# PCB_Ver_1_0.net
KiCad netlist of a schematic drawn in Altium Designer
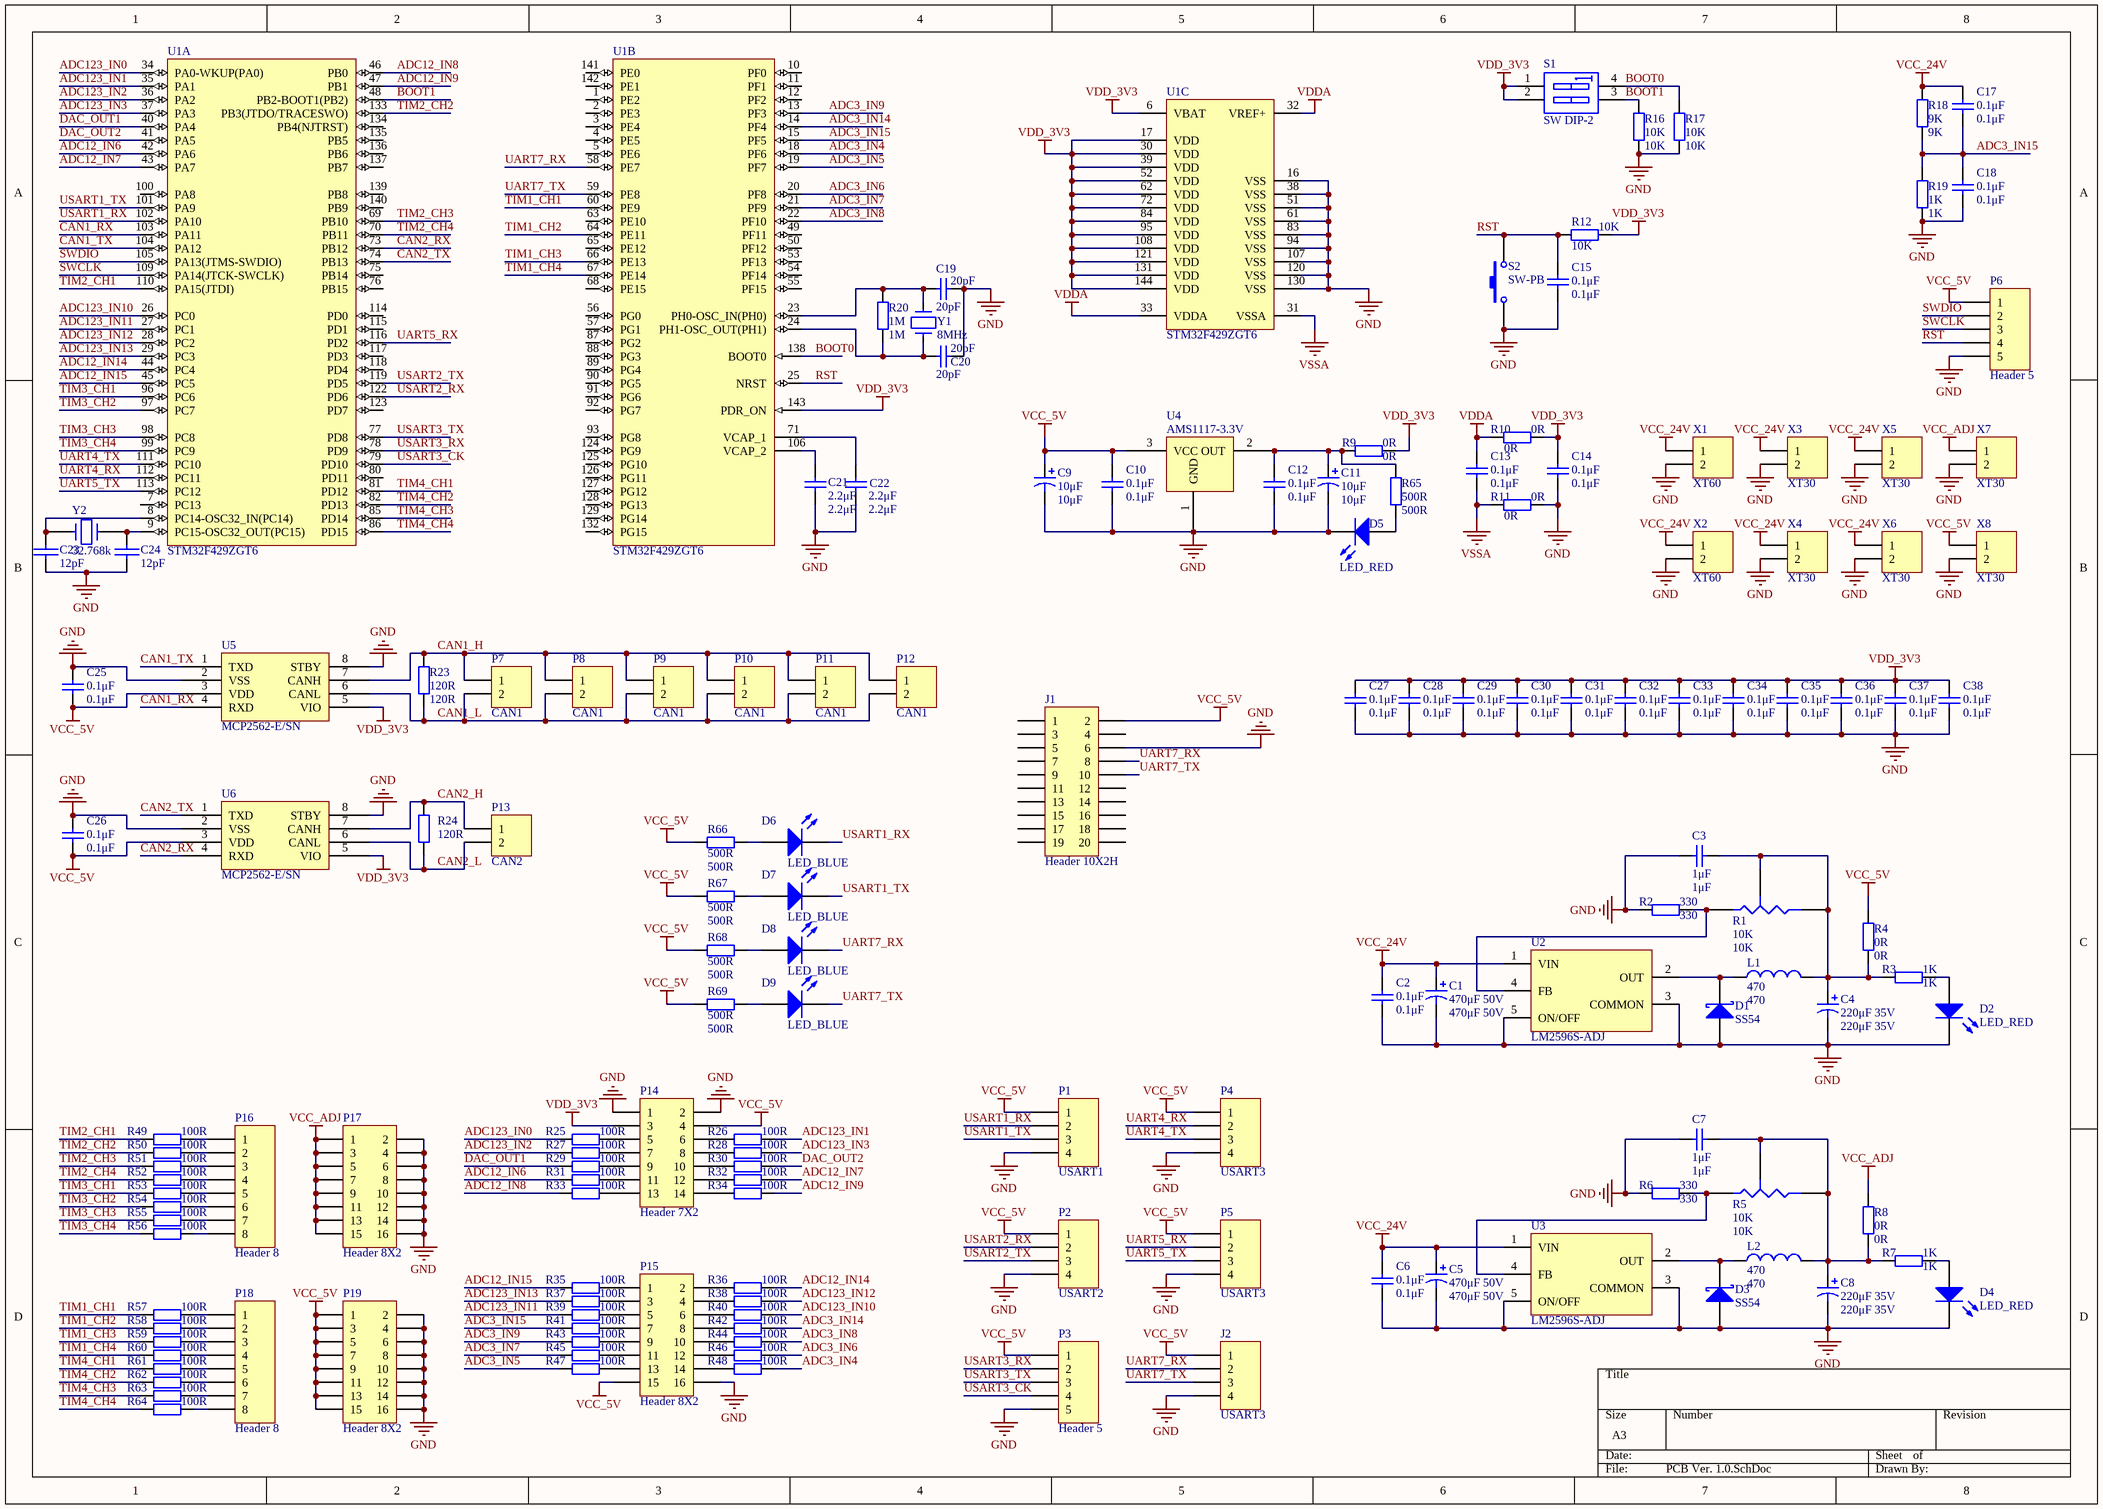
[diagram p0: PCB Ver. 1.0.SchDoc]

(export (version "E")
  (design (tool "Eeschema 10.0.6"))
  (components
    (comp (ref "C1")
      (value "470μF 50V")
      (footprint "RB-.2/.4")
      (description "Polarized Capacitor (Radial)")
      (fields (field (name "ALTIUM_VALUE") "470μF 50V") (field (name "PUBLISHER") "Altium Limited"))
      (libsource (lib "Miscellaneous Devices") (part "Cap Pol1"))
    )
    (comp (ref "C2")
      (value "0.1μF")
      (footprint "0805")
      (description "Capacitor")
      (fields (field (name "ALTIUM_VALUE") "0.1μF") (field (name "PUBLISHER") "Altium Limited"))
      (libsource (lib "Miscellaneous Devices") (part "Cap"))
    )
    (comp (ref "C3")
      (value "1μF")
      (footprint "0805")
      (description "Capacitor")
      (fields (field (name "ALTIUM_VALUE") "1μF") (field (name "PUBLISHER") "Altium Limited"))
      (libsource (lib "Miscellaneous Devices") (part "Cap"))
    )
    (comp (ref "C4")
      (value "220μF 35V")
      (footprint "RB-.2/.4")
      (description "Polarized Capacitor (Radial)")
      (fields (field (name "ALTIUM_VALUE") "220μF 35V") (field (name "PUBLISHER") "Altium Limited"))
      (libsource (lib "Miscellaneous Devices") (part "Cap Pol1"))
    )
    (comp (ref "C5")
      (value "470μF 50V")
      (footprint "RB-.2/.4")
      (description "Polarized Capacitor (Radial)")
      (fields (field (name "ALTIUM_VALUE") "470μF 50V") (field (name "PUBLISHER") "Altium Limited"))
      (libsource (lib "Miscellaneous Devices") (part "Cap Pol1"))
    )
    (comp (ref "C6")
      (value "0.1μF")
      (footprint "0805")
      (description "Capacitor")
      (fields (field (name "ALTIUM_VALUE") "0.1μF") (field (name "PUBLISHER") "Altium Limited"))
      (libsource (lib "Miscellaneous Devices") (part "Cap"))
    )
    (comp (ref "C7")
      (value "1μF")
      (footprint "0805")
      (description "Capacitor")
      (fields (field (name "ALTIUM_VALUE") "1μF") (field (name "PUBLISHER") "Altium Limited"))
      (libsource (lib "Miscellaneous Devices") (part "Cap"))
    )
    (comp (ref "C8")
      (value "220μF 35V")
      (footprint "RB-.2/.4")
      (description "Polarized Capacitor (Radial)")
      (fields (field (name "ALTIUM_VALUE") "220μF 35V") (field (name "PUBLISHER") "Altium Limited"))
      (libsource (lib "Miscellaneous Devices") (part "Cap Pol1"))
    )
    (comp (ref "C9")
      (value "10μF")
      (footprint "0805")
      (description "Polarized Capacitor (Radial)")
      (fields (field (name "ALTIUM_VALUE") "10μF") (field (name "PUBLISHER") "Altium Limited"))
      (libsource (lib "Miscellaneous Devices") (part "Cap Pol1"))
    )
    (comp (ref "C10")
      (value "0.1μF")
      (footprint "0805")
      (description "Capacitor")
      (fields (field (name "ALTIUM_VALUE") "0.1μF") (field (name "PUBLISHER") "Altium Limited"))
      (libsource (lib "Miscellaneous Devices") (part "Cap"))
    )
    (comp (ref "C11")
      (value "10μF")
      (footprint "0805")
      (description "Polarized Capacitor (Radial)")
      (fields (field (name "ALTIUM_VALUE") "10μF") (field (name "PUBLISHER") "Altium Limited"))
      (libsource (lib "Miscellaneous Devices") (part "Cap Pol1"))
    )
    (comp (ref "C12")
      (value "0.1μF")
      (footprint "0805")
      (description "Capacitor")
      (fields (field (name "ALTIUM_VALUE") "0.1μF") (field (name "PUBLISHER") "Altium Limited"))
      (libsource (lib "Miscellaneous Devices") (part "Cap"))
    )
    (comp (ref "C13")
      (value "0.1μF")
      (footprint "0805")
      (description "Capacitor")
      (fields (field (name "ALTIUM_VALUE") "0.1μF") (field (name "PUBLISHER") "Altium Limited"))
      (libsource (lib "Miscellaneous Devices") (part "Cap"))
    )
    (comp (ref "C14")
      (value "0.1μF")
      (footprint "0805")
      (description "Capacitor")
      (fields (field (name "ALTIUM_VALUE") "0.1μF") (field (name "PUBLISHER") "Altium Limited"))
      (libsource (lib "Miscellaneous Devices") (part "Cap"))
    )
    (comp (ref "C15")
      (value "0.1μF")
      (footprint "0805")
      (description "Capacitor")
      (fields (field (name "ALTIUM_VALUE") "0.1μF") (field (name "PUBLISHER") "Altium Limited"))
      (libsource (lib "Miscellaneous Devices") (part "Cap"))
    )
    (comp (ref "C17")
      (value "0.1μF")
      (footprint "0805")
      (description "Capacitor")
      (fields (field (name "ALTIUM_VALUE") "0.1μF") (field (name "PUBLISHER") "Altium Limited"))
      (libsource (lib "Miscellaneous Devices") (part "Cap"))
    )
    (comp (ref "C18")
      (value "0.1μF")
      (footprint "0805")
      (description "Capacitor")
      (fields (field (name "ALTIUM_VALUE") "0.1μF") (field (name "PUBLISHER") "Altium Limited"))
      (libsource (lib "Miscellaneous Devices") (part "Cap"))
    )
    (comp (ref "C19")
      (value "20pF")
      (footprint "0805")
      (description "Capacitor")
      (fields (field (name "ALTIUM_VALUE") "20pF") (field (name "PUBLISHER") "Altium Limited"))
      (libsource (lib "Miscellaneous Devices") (part "Cap"))
    )
    (comp (ref "C20")
      (value "20pF")
      (footprint "0805")
      (description "Capacitor")
      (fields (field (name "ALTIUM_VALUE") "20pF") (field (name "PUBLISHER") "Altium Limited"))
      (libsource (lib "Miscellaneous Devices") (part "Cap"))
    )
    (comp (ref "C21")
      (value "2.2μF")
      (footprint "0805")
      (description "Capacitor")
      (fields (field (name "ALTIUM_VALUE") "2.2μF") (field (name "PUBLISHER") "Altium Limited"))
      (libsource (lib "Miscellaneous Devices") (part "Cap"))
    )
    (comp (ref "C22")
      (value "2.2μF")
      (footprint "0805")
      (description "Capacitor")
      (fields (field (name "ALTIUM_VALUE") "2.2μF") (field (name "PUBLISHER") "Altium Limited"))
      (libsource (lib "Miscellaneous Devices") (part "Cap"))
    )
    (comp (ref "C23")
      (value "12pF")
      (footprint "0805")
      (description "Capcitor")
      (libsource (lib "LXKJSJ") (part "CAP"))
    )
    (comp (ref "C24")
      (value "12pF")
      (footprint "0805")
      (description "Capcitor")
      (libsource (lib "LXKJSJ") (part "CAP"))
    )
    (comp (ref "C25")
      (value "0.1μF")
      (footprint "0805")
      (description "Capacitor")
      (fields (field (name "ALTIUM_VALUE") "0.1μF") (field (name "PUBLISHER") "Altium Limited"))
      (libsource (lib "Miscellaneous Devices") (part "Cap"))
    )
    (comp (ref "C26")
      (value "0.1μF")
      (footprint "0805")
      (description "Capacitor")
      (fields (field (name "ALTIUM_VALUE") "0.1μF") (field (name "PUBLISHER") "Altium Limited"))
      (libsource (lib "Miscellaneous Devices") (part "Cap"))
    )
    (comp (ref "C27")
      (value "0.1μF")
      (footprint "0805")
      (description "Capacitor")
      (fields (field (name "ALTIUM_VALUE") "0.1μF") (field (name "PUBLISHER") "Altium Limited"))
      (libsource (lib "Miscellaneous Devices") (part "Cap"))
    )
    (comp (ref "C28")
      (value "0.1μF")
      (footprint "0805")
      (description "Capacitor")
      (fields (field (name "ALTIUM_VALUE") "0.1μF") (field (name "PUBLISHER") "Altium Limited"))
      (libsource (lib "Miscellaneous Devices") (part "Cap"))
    )
    (comp (ref "C29")
      (value "0.1μF")
      (footprint "0805")
      (description "Capacitor")
      (fields (field (name "ALTIUM_VALUE") "0.1μF") (field (name "PUBLISHER") "Altium Limited"))
      (libsource (lib "Miscellaneous Devices") (part "Cap"))
    )
    (comp (ref "C30")
      (value "0.1μF")
      (footprint "0805")
      (description "Capacitor")
      (fields (field (name "ALTIUM_VALUE") "0.1μF") (field (name "PUBLISHER") "Altium Limited"))
      (libsource (lib "Miscellaneous Devices") (part "Cap"))
    )
    (comp (ref "C31")
      (value "0.1μF")
      (footprint "0805")
      (description "Capacitor")
      (fields (field (name "ALTIUM_VALUE") "0.1μF") (field (name "PUBLISHER") "Altium Limited"))
      (libsource (lib "Miscellaneous Devices") (part "Cap"))
    )
    (comp (ref "C32")
      (value "0.1μF")
      (footprint "0805")
      (description "Capacitor")
      (fields (field (name "ALTIUM_VALUE") "0.1μF") (field (name "PUBLISHER") "Altium Limited"))
      (libsource (lib "Miscellaneous Devices") (part "Cap"))
    )
    (comp (ref "C33")
      (value "0.1μF")
      (footprint "0805")
      (description "Capacitor")
      (fields (field (name "ALTIUM_VALUE") "0.1μF") (field (name "PUBLISHER") "Altium Limited"))
      (libsource (lib "Miscellaneous Devices") (part "Cap"))
    )
    (comp (ref "C34")
      (value "0.1μF")
      (footprint "0805")
      (description "Capacitor")
      (fields (field (name "ALTIUM_VALUE") "0.1μF") (field (name "PUBLISHER") "Altium Limited"))
      (libsource (lib "Miscellaneous Devices") (part "Cap"))
    )
    (comp (ref "C35")
      (value "0.1μF")
      (footprint "0805")
      (description "Capacitor")
      (fields (field (name "ALTIUM_VALUE") "0.1μF") (field (name "PUBLISHER") "Altium Limited"))
      (libsource (lib "Miscellaneous Devices") (part "Cap"))
    )
    (comp (ref "C36")
      (value "0.1μF")
      (footprint "0805")
      (description "Capacitor")
      (fields (field (name "ALTIUM_VALUE") "0.1μF") (field (name "PUBLISHER") "Altium Limited"))
      (libsource (lib "Miscellaneous Devices") (part "Cap"))
    )
    (comp (ref "C37")
      (value "0.1μF")
      (footprint "0805")
      (description "Capacitor")
      (fields (field (name "ALTIUM_VALUE") "0.1μF") (field (name "PUBLISHER") "Altium Limited"))
      (libsource (lib "Miscellaneous Devices") (part "Cap"))
    )
    (comp (ref "C38")
      (value "0.1μF")
      (footprint "0805")
      (description "Capacitor")
      (fields (field (name "ALTIUM_VALUE") "0.1μF") (field (name "PUBLISHER") "Altium Limited"))
      (libsource (lib "Miscellaneous Devices") (part "Cap"))
    )
    (comp (ref "D1")
      (value "SS54")
      (footprint "DO-214AA")
      (description "Schottky Rectifier")
      (fields (field (name "PUBLISHER") "Altium Limited"))
      (libsource (lib "Miscellaneous Devices") (part "Diode 11DQ03"))
    )
    (comp (ref "D2")
      (value "LED_RED")
      (footprint "1206_LED")
      (description "Typical BLUE SiC LED")
      (fields (field (name "PUBLISHER") "Altium Limited"))
      (libsource (lib "Miscellaneous Devices") (part "LED3"))
    )
    (comp (ref "D3")
      (value "SS54")
      (footprint "DO-214AA")
      (description "Schottky Rectifier")
      (fields (field (name "PUBLISHER") "Altium Limited"))
      (libsource (lib "Miscellaneous Devices") (part "Diode 11DQ03"))
    )
    (comp (ref "D4")
      (value "LED_RED")
      (footprint "1206_LED")
      (description "Typical BLUE SiC LED")
      (fields (field (name "PUBLISHER") "Altium Limited"))
      (libsource (lib "Miscellaneous Devices") (part "LED3"))
    )
    (comp (ref "D5")
      (value "LED_RED")
      (footprint "1206_LED")
      (description "Typical BLUE SiC LED")
      (fields (field (name "PUBLISHER") "Altium Limited"))
      (libsource (lib "Miscellaneous Devices") (part "LED3"))
    )
    (comp (ref "D6")
      (value "LED_BLUE")
      (footprint "1206_LED")
      (description "Typical BLUE SiC LED")
      (fields (field (name "PUBLISHER") "Altium Limited"))
      (libsource (lib "Miscellaneous Devices") (part "LED3"))
    )
    (comp (ref "D7")
      (value "LED_BLUE")
      (footprint "1206_LED")
      (description "Typical BLUE SiC LED")
      (fields (field (name "PUBLISHER") "Altium Limited"))
      (libsource (lib "Miscellaneous Devices") (part "LED3"))
    )
    (comp (ref "D8")
      (value "LED_BLUE")
      (footprint "1206_LED")
      (description "Typical BLUE SiC LED")
      (fields (field (name "PUBLISHER") "Altium Limited"))
      (libsource (lib "Miscellaneous Devices") (part "LED3"))
    )
    (comp (ref "D9")
      (value "LED_BLUE")
      (footprint "1206_LED")
      (description "Typical BLUE SiC LED")
      (fields (field (name "PUBLISHER") "Altium Limited"))
      (libsource (lib "Miscellaneous Devices") (part "LED3"))
    )
    (comp (ref "J1")
      (value "Header 10X2H")
      (footprint "HDR2X10")
      (description "Header, 10-Pin, Dual row, Right Angle")
      (fields (field (name "PUBLISHER") "Altium Limited"))
      (libsource (lib "Miscellaneous Connectors") (part "Header 10X2H"))
    )
    (comp (ref "J2")
      (value "USART3")
      (footprint "HDR1X4")
      (description "Header, 4-Pin")
      (fields (field (name "PUBLISHER") "Altium Limited"))
      (libsource (lib "Miscellaneous Connectors") (part "Header 4"))
    )
    (comp (ref "L1")
      (value "470")
      (footprint "12*12*7贴片电感")
      (description "Inductor")
      (fields (field (name "ALTIUM_VALUE") "470") (field (name "PUBLISHER") "Altium Limited"))
      (libsource (lib "Miscellaneous Devices") (part "Inductor"))
    )
    (comp (ref "L2")
      (value "470")
      (footprint "12*12*7贴片电感")
      (description "Inductor")
      (fields (field (name "ALTIUM_VALUE") "470") (field (name "PUBLISHER") "Altium Limited"))
      (libsource (lib "Miscellaneous Devices") (part "Inductor"))
    )
    (comp (ref "P1")
      (value "USART1")
      (footprint "HDR1X4")
      (description "Header, 4-Pin")
      (fields (field (name "PUBLISHER") "Altium Limited"))
      (libsource (lib "Miscellaneous Connectors") (part "Header 4"))
    )
    (comp (ref "P2")
      (value "USART2")
      (footprint "HDR1X4")
      (description "Header, 4-Pin")
      (fields (field (name "PUBLISHER") "Altium Limited"))
      (libsource (lib "Miscellaneous Connectors") (part "Header 4"))
    )
    (comp (ref "P3")
      (value "Header 5")
      (footprint "HDR1X5")
      (description "Header, 5-Pin")
      (fields (field (name "PUBLISHER") "Altium Limited"))
      (libsource (lib "Miscellaneous Connectors") (part "Header 5"))
    )
    (comp (ref "P4")
      (value "USART3")
      (footprint "HDR1X4")
      (description "Header, 4-Pin")
      (fields (field (name "PUBLISHER") "Altium Limited"))
      (libsource (lib "Miscellaneous Connectors") (part "Header 4"))
    )
    (comp (ref "P5")
      (value "USART3")
      (footprint "HDR1X4")
      (description "Header, 4-Pin")
      (fields (field (name "PUBLISHER") "Altium Limited"))
      (libsource (lib "Miscellaneous Connectors") (part "Header 4"))
    )
    (comp (ref "P6")
      (value "Header 5")
      (footprint "HDR1X5")
      (description "Header, 5-Pin")
      (fields (field (name "PUBLISHER") "Altium Limited"))
      (libsource (lib "Miscellaneous Connectors") (part "Header 5"))
    )
    (comp (ref "P7")
      (value "CAN1")
      (footprint "HDR1X2")
      (description "Header, 2-Pin")
      (fields (field (name "PUBLISHER") "Altium Limited"))
      (libsource (lib "Miscellaneous Connectors") (part "Header 2"))
    )
    (comp (ref "P8")
      (value "CAN1")
      (footprint "HDR1X2")
      (description "Header, 2-Pin")
      (fields (field (name "PUBLISHER") "Altium Limited"))
      (libsource (lib "Miscellaneous Connectors") (part "Header 2"))
    )
    (comp (ref "P9")
      (value "CAN1")
      (footprint "HDR1X2")
      (description "Header, 2-Pin")
      (fields (field (name "PUBLISHER") "Altium Limited"))
      (libsource (lib "Miscellaneous Connectors") (part "Header 2"))
    )
    (comp (ref "P10")
      (value "CAN1")
      (footprint "HDR1X2")
      (description "Header, 2-Pin")
      (fields (field (name "PUBLISHER") "Altium Limited"))
      (libsource (lib "Miscellaneous Connectors") (part "Header 2"))
    )
    (comp (ref "P11")
      (value "CAN1")
      (footprint "HDR1X2")
      (description "Header, 2-Pin")
      (fields (field (name "PUBLISHER") "Altium Limited"))
      (libsource (lib "Miscellaneous Connectors") (part "Header 2"))
    )
    (comp (ref "P12")
      (value "CAN1")
      (footprint "HDR1X2")
      (description "Header, 2-Pin")
      (fields (field (name "PUBLISHER") "Altium Limited"))
      (libsource (lib "Miscellaneous Connectors") (part "Header 2"))
    )
    (comp (ref "P13")
      (value "CAN2")
      (footprint "HDR1X2")
      (description "Header, 2-Pin")
      (fields (field (name "PUBLISHER") "Altium Limited"))
      (libsource (lib "Miscellaneous Connectors") (part "Header 2"))
    )
    (comp (ref "P14")
      (value "Header 7X2")
      (footprint "HDR2X7")
      (description "Header, 7-Pin, Dual row")
      (fields (field (name "PUBLISHER") "Altium Limited"))
      (libsource (lib "Miscellaneous Connectors") (part "Header 7X2"))
    )
    (comp (ref "P15")
      (value "Header 8X2")
      (footprint "HDR2X8")
      (description "Header, 8-Pin, Dual row")
      (fields (field (name "PUBLISHER") "Altium Limited"))
      (libsource (lib "Miscellaneous Connectors") (part "Header 8X2"))
    )
    (comp (ref "P16")
      (value "Header 8")
      (footprint "HDR1X8")
      (description "Header, 8-Pin")
      (fields (field (name "PUBLISHER") "Altium Limited"))
      (libsource (lib "Miscellaneous Connectors") (part "Header 8"))
    )
    (comp (ref "P17")
      (value "Header 8X2")
      (footprint "HDR2X8")
      (description "Header, 8-Pin, Dual row")
      (fields (field (name "PUBLISHER") "Altium Limited"))
      (libsource (lib "Miscellaneous Connectors") (part "Header 8X2"))
    )
    (comp (ref "P18")
      (value "Header 8")
      (footprint "HDR1X8")
      (description "Header, 8-Pin")
      (fields (field (name "PUBLISHER") "Altium Limited"))
      (libsource (lib "Miscellaneous Connectors") (part "Header 8"))
    )
    (comp (ref "P19")
      (value "Header 8X2")
      (footprint "HDR2X8")
      (description "Header, 8-Pin, Dual row")
      (fields (field (name "PUBLISHER") "Altium Limited"))
      (libsource (lib "Miscellaneous Connectors") (part "Header 8X2"))
    )
    (comp (ref "R1")
      (value "10K")
      (footprint "3296")
      (description "Tapped Resistor")
      (fields (field (name "ALTIUM_VALUE") "10K") (field (name "PUBLISHER") "Altium Limited"))
      (libsource (lib "Miscellaneous Devices") (part "Res Tap"))
    )
    (comp (ref "R2")
      (value "330")
      (footprint "0805")
      (description "Resistor")
      (fields (field (name "ALTIUM_VALUE") "330") (field (name "PUBLISHER") "Altium Limited"))
      (libsource (lib "Miscellaneous Devices") (part "Res2"))
    )
    (comp (ref "R3")
      (value "1K")
      (footprint "0805")
      (description "Resistor")
      (fields (field (name "ALTIUM_VALUE") "1K") (field (name "PUBLISHER") "Altium Limited"))
      (libsource (lib "Miscellaneous Devices") (part "Res2"))
    )
    (comp (ref "R4")
      (value "0R")
      (footprint "0805")
      (description "Resistor")
      (fields (field (name "ALTIUM_VALUE") "0R") (field (name "PUBLISHER") "Altium Limited"))
      (libsource (lib "") (part "Res2_1"))
    )
    (comp (ref "R5")
      (value "10K")
      (footprint "3296")
      (description "Tapped Resistor")
      (fields (field (name "ALTIUM_VALUE") "10K") (field (name "PUBLISHER") "Altium Limited"))
      (libsource (lib "Miscellaneous Devices") (part "Res Tap"))
    )
    (comp (ref "R6")
      (value "330")
      (footprint "0805")
      (description "Resistor")
      (fields (field (name "ALTIUM_VALUE") "330") (field (name "PUBLISHER") "Altium Limited"))
      (libsource (lib "Miscellaneous Devices") (part "Res2"))
    )
    (comp (ref "R7")
      (value "1K")
      (footprint "0805")
      (description "Resistor")
      (fields (field (name "ALTIUM_VALUE") "1K") (field (name "PUBLISHER") "Altium Limited"))
      (libsource (lib "Miscellaneous Devices") (part "Res2"))
    )
    (comp (ref "R8")
      (value "0R")
      (footprint "0805")
      (description "Resistor")
      (fields (field (name "ALTIUM_VALUE") "0R") (field (name "PUBLISHER") "Altium Limited"))
      (libsource (lib "") (part "Res2_1"))
    )
    (comp (ref "R9")
      (value "0R")
      (footprint "0805")
      (description "Resistor")
      (fields (field (name "ALTIUM_VALUE") "0R") (field (name "PUBLISHER") "Altium Limited"))
      (libsource (lib "Miscellaneous Devices") (part "Res2"))
    )
    (comp (ref "R10")
      (value "0R")
      (footprint "0805")
      (description "Resistor")
      (fields (field (name "ALTIUM_VALUE") "0R") (field (name "PUBLISHER") "Altium Limited"))
      (libsource (lib "Miscellaneous Devices") (part "Res2"))
    )
    (comp (ref "R11")
      (value "0R")
      (footprint "0805")
      (description "Resistor")
      (fields (field (name "ALTIUM_VALUE") "0R") (field (name "PUBLISHER") "Altium Limited"))
      (libsource (lib "Miscellaneous Devices") (part "Res2"))
    )
    (comp (ref "R12")
      (value "10K")
      (footprint "0805")
      (description "Resistor")
      (fields (field (name "ALTIUM_VALUE") "10K") (field (name "PUBLISHER") "Altium Limited"))
      (libsource (lib "Miscellaneous Devices") (part "Res2"))
    )
    (comp (ref "R16")
      (value "10K")
      (footprint "0805")
      (description "Resistor")
      (fields (field (name "ALTIUM_VALUE") "10K") (field (name "PUBLISHER") "Altium Limited"))
      (libsource (lib "") (part "Res2_1"))
    )
    (comp (ref "R17")
      (value "10K")
      (footprint "0805")
      (description "Resistor")
      (fields (field (name "ALTIUM_VALUE") "10K") (field (name "PUBLISHER") "Altium Limited"))
      (libsource (lib "") (part "Res2_1"))
    )
    (comp (ref "R18")
      (value "9K")
      (footprint "0805")
      (description "Resistor")
      (fields (field (name "ALTIUM_VALUE") "9K") (field (name "PUBLISHER") "Altium Limited"))
      (libsource (lib "") (part "Res2_1"))
    )
    (comp (ref "R19")
      (value "1K")
      (footprint "0805")
      (description "Resistor")
      (fields (field (name "ALTIUM_VALUE") "1K") (field (name "PUBLISHER") "Altium Limited"))
      (libsource (lib "") (part "Res2_1"))
    )
    (comp (ref "R20")
      (value "1M")
      (footprint "0805")
      (description "Resistor")
      (fields (field (name "ALTIUM_VALUE") "1M") (field (name "PUBLISHER") "Altium Limited"))
      (libsource (lib "") (part "Res2_1"))
    )
    (comp (ref "R23")
      (value "120R")
      (footprint "0805")
      (description "Resistor")
      (fields (field (name "ALTIUM_VALUE") "120R") (field (name "PUBLISHER") "Altium Limited"))
      (libsource (lib "") (part "Res2_1"))
    )
    (comp (ref "R24")
      (value "120R")
      (footprint "0805")
      (description "Resistor")
      (fields (field (name "PUBLISHER") "Altium Limited"))
      (libsource (lib "") (part "Res2_1"))
    )
    (comp (ref "R25")
      (value "100R")
      (footprint "0805")
      (description "Resistor")
      (fields (field (name "PUBLISHER") "Altium Limited"))
      (libsource (lib "Miscellaneous Devices") (part "Res2"))
    )
    (comp (ref "R26")
      (value "100R")
      (footprint "0805")
      (description "Resistor")
      (fields (field (name "PUBLISHER") "Altium Limited"))
      (libsource (lib "Miscellaneous Devices") (part "Res2"))
    )
    (comp (ref "R27")
      (value "100R")
      (footprint "0805")
      (description "Resistor")
      (fields (field (name "PUBLISHER") "Altium Limited"))
      (libsource (lib "Miscellaneous Devices") (part "Res2"))
    )
    (comp (ref "R28")
      (value "100R")
      (footprint "0805")
      (description "Resistor")
      (fields (field (name "PUBLISHER") "Altium Limited"))
      (libsource (lib "Miscellaneous Devices") (part "Res2"))
    )
    (comp (ref "R29")
      (value "100R")
      (footprint "0805")
      (description "Resistor")
      (fields (field (name "PUBLISHER") "Altium Limited"))
      (libsource (lib "Miscellaneous Devices") (part "Res2"))
    )
    (comp (ref "R30")
      (value "100R")
      (footprint "0805")
      (description "Resistor")
      (fields (field (name "PUBLISHER") "Altium Limited"))
      (libsource (lib "Miscellaneous Devices") (part "Res2"))
    )
    (comp (ref "R31")
      (value "100R")
      (footprint "0805")
      (description "Resistor")
      (fields (field (name "PUBLISHER") "Altium Limited"))
      (libsource (lib "Miscellaneous Devices") (part "Res2"))
    )
    (comp (ref "R32")
      (value "100R")
      (footprint "0805")
      (description "Resistor")
      (fields (field (name "PUBLISHER") "Altium Limited"))
      (libsource (lib "Miscellaneous Devices") (part "Res2"))
    )
    (comp (ref "R33")
      (value "100R")
      (footprint "0805")
      (description "Resistor")
      (fields (field (name "PUBLISHER") "Altium Limited"))
      (libsource (lib "Miscellaneous Devices") (part "Res2"))
    )
    (comp (ref "R34")
      (value "100R")
      (footprint "0805")
      (description "Resistor")
      (fields (field (name "PUBLISHER") "Altium Limited"))
      (libsource (lib "Miscellaneous Devices") (part "Res2"))
    )
    (comp (ref "R35")
      (value "100R")
      (footprint "0805")
      (description "Resistor")
      (fields (field (name "PUBLISHER") "Altium Limited"))
      (libsource (lib "Miscellaneous Devices") (part "Res2"))
    )
    (comp (ref "R36")
      (value "100R")
      (footprint "0805")
      (description "Resistor")
      (fields (field (name "PUBLISHER") "Altium Limited"))
      (libsource (lib "Miscellaneous Devices") (part "Res2"))
    )
    (comp (ref "R37")
      (value "100R")
      (footprint "0805")
      (description "Resistor")
      (fields (field (name "PUBLISHER") "Altium Limited"))
      (libsource (lib "Miscellaneous Devices") (part "Res2"))
    )
    (comp (ref "R38")
      (value "100R")
      (footprint "0805")
      (description "Resistor")
      (fields (field (name "PUBLISHER") "Altium Limited"))
      (libsource (lib "Miscellaneous Devices") (part "Res2"))
    )
    (comp (ref "R39")
      (value "100R")
      (footprint "0805")
      (description "Resistor")
      (fields (field (name "PUBLISHER") "Altium Limited"))
      (libsource (lib "Miscellaneous Devices") (part "Res2"))
    )
    (comp (ref "R40")
      (value "100R")
      (footprint "0805")
      (description "Resistor")
      (fields (field (name "PUBLISHER") "Altium Limited"))
      (libsource (lib "Miscellaneous Devices") (part "Res2"))
    )
    (comp (ref "R41")
      (value "100R")
      (footprint "0805")
      (description "Resistor")
      (fields (field (name "PUBLISHER") "Altium Limited"))
      (libsource (lib "Miscellaneous Devices") (part "Res2"))
    )
    (comp (ref "R42")
      (value "100R")
      (footprint "0805")
      (description "Resistor")
      (fields (field (name "PUBLISHER") "Altium Limited"))
      (libsource (lib "Miscellaneous Devices") (part "Res2"))
    )
    (comp (ref "R43")
      (value "100R")
      (footprint "0805")
      (description "Resistor")
      (fields (field (name "PUBLISHER") "Altium Limited"))
      (libsource (lib "Miscellaneous Devices") (part "Res2"))
    )
    (comp (ref "R44")
      (value "100R")
      (footprint "0805")
      (description "Resistor")
      (fields (field (name "PUBLISHER") "Altium Limited"))
      (libsource (lib "Miscellaneous Devices") (part "Res2"))
    )
    (comp (ref "R45")
      (value "100R")
      (footprint "0805")
      (description "Resistor")
      (fields (field (name "PUBLISHER") "Altium Limited"))
      (libsource (lib "Miscellaneous Devices") (part "Res2"))
    )
    (comp (ref "R46")
      (value "100R")
      (footprint "0805")
      (description "Resistor")
      (fields (field (name "PUBLISHER") "Altium Limited"))
      (libsource (lib "Miscellaneous Devices") (part "Res2"))
    )
    (comp (ref "R47")
      (value "100R")
      (footprint "0805")
      (description "Resistor")
      (fields (field (name "PUBLISHER") "Altium Limited"))
      (libsource (lib "Miscellaneous Devices") (part "Res2"))
    )
    (comp (ref "R48")
      (value "100R")
      (footprint "0805")
      (description "Resistor")
      (fields (field (name "PUBLISHER") "Altium Limited"))
      (libsource (lib "Miscellaneous Devices") (part "Res2"))
    )
    (comp (ref "R49")
      (value "100R")
      (footprint "0805")
      (description "Resistor")
      (fields (field (name "PUBLISHER") "Altium Limited"))
      (libsource (lib "Miscellaneous Devices") (part "Res2"))
    )
    (comp (ref "R50")
      (value "100R")
      (footprint "0805")
      (description "Resistor")
      (fields (field (name "PUBLISHER") "Altium Limited"))
      (libsource (lib "Miscellaneous Devices") (part "Res2"))
    )
    (comp (ref "R51")
      (value "100R")
      (footprint "0805")
      (description "Resistor")
      (fields (field (name "PUBLISHER") "Altium Limited"))
      (libsource (lib "Miscellaneous Devices") (part "Res2"))
    )
    (comp (ref "R52")
      (value "100R")
      (footprint "0805")
      (description "Resistor")
      (fields (field (name "PUBLISHER") "Altium Limited"))
      (libsource (lib "Miscellaneous Devices") (part "Res2"))
    )
    (comp (ref "R53")
      (value "100R")
      (footprint "0805")
      (description "Resistor")
      (fields (field (name "PUBLISHER") "Altium Limited"))
      (libsource (lib "Miscellaneous Devices") (part "Res2"))
    )
    (comp (ref "R54")
      (value "100R")
      (footprint "0805")
      (description "Resistor")
      (fields (field (name "PUBLISHER") "Altium Limited"))
      (libsource (lib "Miscellaneous Devices") (part "Res2"))
    )
    (comp (ref "R55")
      (value "100R")
      (footprint "0805")
      (description "Resistor")
      (fields (field (name "PUBLISHER") "Altium Limited"))
      (libsource (lib "Miscellaneous Devices") (part "Res2"))
    )
    (comp (ref "R56")
      (value "100R")
      (footprint "0805")
      (description "Resistor")
      (fields (field (name "PUBLISHER") "Altium Limited"))
      (libsource (lib "Miscellaneous Devices") (part "Res2"))
    )
    (comp (ref "R57")
      (value "100R")
      (footprint "0805")
      (description "Resistor")
      (fields (field (name "PUBLISHER") "Altium Limited"))
      (libsource (lib "Miscellaneous Devices") (part "Res2"))
    )
    (comp (ref "R58")
      (value "100R")
      (footprint "0805")
      (description "Resistor")
      (fields (field (name "PUBLISHER") "Altium Limited"))
      (libsource (lib "Miscellaneous Devices") (part "Res2"))
    )
    (comp (ref "R59")
      (value "100R")
      (footprint "0805")
      (description "Resistor")
      (fields (field (name "PUBLISHER") "Altium Limited"))
      (libsource (lib "Miscellaneous Devices") (part "Res2"))
    )
    (comp (ref "R60")
      (value "100R")
      (footprint "0805")
      (description "Resistor")
      (fields (field (name "PUBLISHER") "Altium Limited"))
      (libsource (lib "Miscellaneous Devices") (part "Res2"))
    )
    (comp (ref "R61")
      (value "100R")
      (footprint "0805")
      (description "Resistor")
      (fields (field (name "PUBLISHER") "Altium Limited"))
      (libsource (lib "Miscellaneous Devices") (part "Res2"))
    )
    (comp (ref "R62")
      (value "100R")
      (footprint "0805")
      (description "Resistor")
      (fields (field (name "PUBLISHER") "Altium Limited"))
      (libsource (lib "Miscellaneous Devices") (part "Res2"))
    )
    (comp (ref "R63")
      (value "100R")
      (footprint "0805")
      (description "Resistor")
      (fields (field (name "PUBLISHER") "Altium Limited"))
      (libsource (lib "Miscellaneous Devices") (part "Res2"))
    )
    (comp (ref "R64")
      (value "100R")
      (footprint "0805")
      (description "Resistor")
      (fields (field (name "PUBLISHER") "Altium Limited"))
      (libsource (lib "Miscellaneous Devices") (part "Res2"))
    )
    (comp (ref "R65")
      (value "500R")
      (footprint "0805")
      (description "Resistor")
      (fields (field (name "ALTIUM_VALUE") "500R") (field (name "PUBLISHER") "Altium Limited"))
      (libsource (lib "") (part "Res2_1"))
    )
    (comp (ref "R66")
      (value "500R")
      (footprint "0805")
      (description "Resistor")
      (fields (field (name "ALTIUM_VALUE") "500R") (field (name "PUBLISHER") "Altium Limited"))
      (libsource (lib "") (part "Res2_2"))
    )
    (comp (ref "R67")
      (value "500R")
      (footprint "0805")
      (description "Resistor")
      (fields (field (name "ALTIUM_VALUE") "500R") (field (name "PUBLISHER") "Altium Limited"))
      (libsource (lib "") (part "Res2_2"))
    )
    (comp (ref "R68")
      (value "500R")
      (footprint "0805")
      (description "Resistor")
      (fields (field (name "ALTIUM_VALUE") "500R") (field (name "PUBLISHER") "Altium Limited"))
      (libsource (lib "") (part "Res2_2"))
    )
    (comp (ref "R69")
      (value "500R")
      (footprint "0805")
      (description "Resistor")
      (fields (field (name "ALTIUM_VALUE") "500R") (field (name "PUBLISHER") "Altium Limited"))
      (libsource (lib "") (part "Res2_2"))
    )
    (comp (ref "S1")
      (value "SW DIP-2")
      (footprint "DIP-4")
      (description "DIP Switch, 2 Position, SPST")
      (fields (field (name "PUBLISHER") "Altium Limited"))
      (libsource (lib "Miscellaneous Devices") (part "SW DIP-2"))
    )
    (comp (ref "S2")
      (value "SW-PB")
      (footprint "3*6 开关")
      (description "Switch")
      (fields (field (name "PUBLISHER") "Altium Limited"))
      (libsource (lib "Miscellaneous Devices") (part "SW-PB"))
    )
    (comp (ref "U1")
      (value "STM32F429ZGT6")
      (footprint "STM-LQFP144_N")
      (fields (field (name "MANUFACTURER") "STMicroelectronics"))
      (libsource (lib "STMicroelectronics STM32 F4") (part "STM32F429ZGT6"))
    )
    (comp (ref "U2")
      (value "LM2596S-ADJ")
      (footprint "TO-263")
      (description "CI-LM2576S-5.0")
      (libsource (lib "IC") (part "LM2576S-5.0"))
    )
    (comp (ref "U3")
      (value "LM2596S-ADJ")
      (footprint "TO-263")
      (description "CI-LM2576S-5.0")
      (libsource (lib "IC") (part "LM2576S-5.0"))
    )
    (comp (ref "U4") (value "AMS1117-3.3V") (footprint "SOT223") (libsource (lib "*") (part "11")))
    (comp (ref "U5")
      (value "MCP2562-E/SN")
      (footprint "SO-8")
      (libsource (lib "TempLibraries") (part "MCP2562-E/MF"))
    )
    (comp (ref "U6")
      (value "MCP2562-E/SN")
      (footprint "SO-8")
      (libsource (lib "TempLibraries") (part "MCP2562-E/MF"))
    )
    (comp (ref "X1")
      (value "XT60")
      (footprint "XT60PB")
      (description "Header, 2-Pin")
      (fields (field (name "PUBLISHER") "Altium Limited"))
      (libsource (lib "Miscellaneous Connectors") (part "Header 2"))
    )
    (comp (ref "X2")
      (value "XT60")
      (footprint "XT60PB")
      (description "Header, 2-Pin")
      (fields (field (name "PUBLISHER") "Altium Limited"))
      (libsource (lib "Miscellaneous Connectors") (part "Header 2"))
    )
    (comp (ref "X3")
      (value "XT30")
      (footprint "XT30UPB")
      (description "Header, 2-Pin")
      (fields (field (name "PUBLISHER") "Altium Limited"))
      (libsource (lib "Miscellaneous Connectors") (part "Header 2"))
    )
    (comp (ref "X4")
      (value "XT30")
      (footprint "XT30UPB")
      (description "Header, 2-Pin")
      (fields (field (name "PUBLISHER") "Altium Limited"))
      (libsource (lib "Miscellaneous Connectors") (part "Header 2"))
    )
    (comp (ref "X5")
      (value "XT30")
      (footprint "XT30UPB")
      (description "Header, 2-Pin")
      (fields (field (name "PUBLISHER") "Altium Limited"))
      (libsource (lib "Miscellaneous Connectors") (part "Header 2"))
    )
    (comp (ref "X6")
      (value "XT30")
      (footprint "XT30UPB")
      (description "Header, 2-Pin")
      (fields (field (name "PUBLISHER") "Altium Limited"))
      (libsource (lib "Miscellaneous Connectors") (part "Header 2"))
    )
    (comp (ref "X7")
      (value "XT30")
      (footprint "XT30UPB")
      (description "Header, 2-Pin")
      (fields (field (name "PUBLISHER") "Altium Limited"))
      (libsource (lib "Miscellaneous Connectors") (part "Header 2"))
    )
    (comp (ref "X8")
      (value "XT30")
      (footprint "XT30UPB")
      (description "Header, 2-Pin")
      (fields (field (name "PUBLISHER") "Altium Limited"))
      (libsource (lib "Miscellaneous Connectors") (part "Header 2"))
    )
    (comp (ref "Y1")
      (value "8MHz")
      (footprint "XTAL")
      (description "Crystal Oscillator")
      (libsource (lib "LXKJSJ") (part "XTAL"))
    )
    (comp (ref "Y2")
      (value "32.768k")
      (footprint "MHDR1X2")
      (description "Crystal 8MHz PLUG")
      (libsource (lib "*") (part "CRYSTAL"))
    )
  )
  (nets
    (net (code "2") (name "/ADC3_IN4") (class "Default")
      (node (ref "R48") (pin "2") (pinfunction "2_2") (pintype "passive"))
      (node (ref "U1") (pin "18") (pinfunction "PF6_18") (pintype "bidirectional"))
    )
    (net (code "3") (name "/ADC3_IN5") (class "Default")
      (node (ref "R47") (pin "1") (pinfunction "1_1") (pintype "passive"))
      (node (ref "U1") (pin "19") (pinfunction "PF7_19") (pintype "bidirectional"))
    )
    (net (code "4") (name "/ADC3_IN6") (class "Default")
      (node (ref "R46") (pin "2") (pinfunction "2_2") (pintype "passive"))
      (node (ref "U1") (pin "20") (pinfunction "PF8_20") (pintype "bidirectional"))
    )
    (net (code "5") (name "/ADC3_IN7") (class "Default")
      (node (ref "R45") (pin "1") (pinfunction "1_1") (pintype "passive"))
      (node (ref "U1") (pin "21") (pinfunction "PF9_21") (pintype "bidirectional"))
    )
    (net (code "6") (name "/ADC3_IN8") (class "Default")
      (node (ref "R44") (pin "2") (pinfunction "2_2") (pintype "passive"))
      (node (ref "U1") (pin "22") (pinfunction "PF10_22") (pintype "bidirectional"))
    )
    (net (code "7") (name "/ADC3_IN9") (class "Default")
      (node (ref "R43") (pin "1") (pinfunction "1_1") (pintype "passive"))
      (node (ref "U1") (pin "13") (pinfunction "PF3_13") (pintype "bidirectional"))
    )
    (net (code "8") (name "/ADC3_IN14") (class "Default")
      (node (ref "R42") (pin "2") (pinfunction "2_2") (pintype "passive"))
      (node (ref "U1") (pin "14") (pinfunction "PF4_14") (pintype "bidirectional"))
    )
    (net (code "9") (name "/ADC3_IN15") (class "Default")
      (node (ref "C17") (pin "1") (pinfunction "1_1") (pintype "passive"))
      (node (ref "C18") (pin "2") (pinfunction "2_2") (pintype "passive"))
      (node (ref "R18") (pin "1") (pinfunction "1_1") (pintype "passive"))
      (node (ref "R19") (pin "2") (pinfunction "2_2") (pintype "passive"))
      (node (ref "R41") (pin "1") (pinfunction "1_1") (pintype "passive"))
      (node (ref "U1") (pin "15") (pinfunction "PF5_15") (pintype "bidirectional"))
    )
    (net (code "10") (name "/ADC12_IN6") (class "Default")
      (node (ref "R31") (pin "1") (pinfunction "1_1") (pintype "passive"))
      (node (ref "U1") (pin "42") (pinfunction "PA6_42") (pintype "bidirectional"))
    )
    (net (code "11") (name "/ADC12_IN7") (class "Default")
      (node (ref "R32") (pin "2") (pinfunction "2_2") (pintype "passive"))
      (node (ref "U1") (pin "43") (pinfunction "PA7_43") (pintype "bidirectional"))
    )
    (net (code "12") (name "/ADC12_IN8") (class "Default")
      (node (ref "R33") (pin "1") (pinfunction "1_1") (pintype "passive"))
      (node (ref "U1") (pin "46") (pinfunction "PB0_46") (pintype "bidirectional"))
    )
    (net (code "13") (name "/ADC12_IN9") (class "Default")
      (node (ref "R34") (pin "2") (pinfunction "2_2") (pintype "passive"))
      (node (ref "U1") (pin "47") (pinfunction "PB1_47") (pintype "bidirectional"))
    )
    (net (code "14") (name "/ADC12_IN14") (class "Default")
      (node (ref "R36") (pin "2") (pinfunction "2_2") (pintype "passive"))
      (node (ref "U1") (pin "44") (pinfunction "PC4_44") (pintype "bidirectional"))
    )
    (net (code "15") (name "/ADC12_IN15") (class "Default")
      (node (ref "R35") (pin "1") (pinfunction "1_1") (pintype "passive"))
      (node (ref "U1") (pin "45") (pinfunction "PC5_45") (pintype "bidirectional"))
    )
    (net (code "16") (name "/ADC123_IN0") (class "Default")
      (node (ref "R25") (pin "1") (pinfunction "1_1") (pintype "passive"))
      (node (ref "U1") (pin "34") (pinfunction "PA0-WKUP(PA0)_34") (pintype "bidirectional"))
    )
    (net (code "17") (name "/ADC123_IN1") (class "Default")
      (node (ref "R26") (pin "2") (pinfunction "2_2") (pintype "passive"))
      (node (ref "U1") (pin "35") (pinfunction "PA1_35") (pintype "bidirectional"))
    )
    (net (code "18") (name "/ADC123_IN2") (class "Default")
      (node (ref "R27") (pin "1") (pinfunction "1_1") (pintype "passive"))
      (node (ref "U1") (pin "36") (pinfunction "PA2_36") (pintype "bidirectional"))
    )
    (net (code "19") (name "/ADC123_IN3") (class "Default")
      (node (ref "R28") (pin "2") (pinfunction "2_2") (pintype "passive"))
      (node (ref "U1") (pin "37") (pinfunction "PA3_37") (pintype "bidirectional"))
    )
    (net (code "20") (name "/ADC123_IN10") (class "Default")
      (node (ref "R40") (pin "2") (pinfunction "2_2") (pintype "passive"))
      (node (ref "U1") (pin "26") (pinfunction "PC0_26") (pintype "bidirectional"))
    )
    (net (code "21") (name "/ADC123_IN11") (class "Default")
      (node (ref "R39") (pin "1") (pinfunction "1_1") (pintype "passive"))
      (node (ref "U1") (pin "27") (pinfunction "PC1_27") (pintype "bidirectional"))
    )
    (net (code "22") (name "/ADC123_IN12") (class "Default")
      (node (ref "R38") (pin "2") (pinfunction "2_2") (pintype "passive"))
      (node (ref "U1") (pin "28") (pinfunction "PC2_28") (pintype "bidirectional"))
    )
    (net (code "23") (name "/ADC123_IN13") (class "Default")
      (node (ref "R37") (pin "1") (pinfunction "1_1") (pintype "passive"))
      (node (ref "U1") (pin "29") (pinfunction "PC3_29") (pintype "bidirectional"))
    )
    (net (code "24") (name "/BOOT0") (class "Default")
      (node (ref "R17") (pin "2") (pinfunction "2_2") (pintype "passive"))
      (node (ref "S1") (pin "4") (pinfunction "B1_4") (pintype "passive"))
      (node (ref "U1") (pin "138") (pinfunction "BOOT0_138") (pintype "input"))
    )
    (net (code "25") (name "/BOOT1") (class "Default")
      (node (ref "R16") (pin "2") (pinfunction "2_2") (pintype "passive"))
      (node (ref "S1") (pin "3") (pinfunction "B2_3") (pintype "passive"))
      (node (ref "U1") (pin "48") (pinfunction "PB2-BOOT1(PB2)_48") (pintype "bidirectional"))
    )
    (net (code "26") (name "/CAN1_H") (class "Default")
      (node (ref "P10") (pin "1") (pinfunction "1_1") (pintype "passive"))
      (node (ref "P11") (pin "1") (pinfunction "1_1") (pintype "passive"))
      (node (ref "P12") (pin "1") (pinfunction "1_1") (pintype "passive"))
      (node (ref "P7") (pin "1") (pinfunction "1_1") (pintype "passive"))
      (node (ref "P8") (pin "1") (pinfunction "1_1") (pintype "passive"))
      (node (ref "P9") (pin "1") (pinfunction "1_1") (pintype "passive"))
      (node (ref "R23") (pin "2") (pinfunction "2_2") (pintype "passive"))
      (node (ref "U5") (pin "7") (pinfunction "CANH_7") (pintype "passive"))
    )
    (net (code "27") (name "/CAN1_L") (class "Default")
      (node (ref "P10") (pin "2") (pinfunction "2_2") (pintype "passive"))
      (node (ref "P11") (pin "2") (pinfunction "2_2") (pintype "passive"))
      (node (ref "P12") (pin "2") (pinfunction "2_2") (pintype "passive"))
      (node (ref "P7") (pin "2") (pinfunction "2_2") (pintype "passive"))
      (node (ref "P8") (pin "2") (pinfunction "2_2") (pintype "passive"))
      (node (ref "P9") (pin "2") (pinfunction "2_2") (pintype "passive"))
      (node (ref "R23") (pin "1") (pinfunction "1_1") (pintype "passive"))
      (node (ref "U5") (pin "6") (pinfunction "CANL_6") (pintype "passive"))
    )
    (net (code "28") (name "/CAN1_RX") (class "Default")
      (node (ref "U1") (pin "103") (pinfunction "PA11_103") (pintype "bidirectional"))
      (node (ref "U5") (pin "4") (pinfunction "RXD_4") (pintype "passive"))
    )
    (net (code "29") (name "/CAN1_TX") (class "Default")
      (node (ref "U1") (pin "104") (pinfunction "PA12_104") (pintype "bidirectional"))
      (node (ref "U5") (pin "1") (pinfunction "TXD_1") (pintype "passive"))
    )
    (net (code "30") (name "/CAN2_H") (class "Default")
      (node (ref "P13") (pin "1") (pinfunction "1_1") (pintype "passive"))
      (node (ref "R24") (pin "2") (pinfunction "2_2") (pintype "passive"))
      (node (ref "U6") (pin "7") (pinfunction "CANH_7") (pintype "passive"))
    )
    (net (code "31") (name "/CAN2_L") (class "Default")
      (node (ref "P13") (pin "2") (pinfunction "2_2") (pintype "passive"))
      (node (ref "R24") (pin "1") (pinfunction "1_1") (pintype "passive"))
      (node (ref "U6") (pin "6") (pinfunction "CANL_6") (pintype "passive"))
    )
    (net (code "32") (name "/CAN2_RX") (class "Default")
      (node (ref "U1") (pin "73") (pinfunction "PB12_73") (pintype "bidirectional"))
      (node (ref "U6") (pin "4") (pinfunction "RXD_4") (pintype "passive"))
    )
    (net (code "33") (name "/CAN2_TX") (class "Default")
      (node (ref "U1") (pin "74") (pinfunction "PB13_74") (pintype "bidirectional"))
      (node (ref "U6") (pin "1") (pinfunction "TXD_1") (pintype "passive"))
    )
    (net (code "34") (name "/DAC_OUT1") (class "Default")
      (node (ref "R29") (pin "1") (pinfunction "1_1") (pintype "passive"))
      (node (ref "U1") (pin "40") (pinfunction "PA4_40") (pintype "bidirectional"))
    )
    (net (code "35") (name "/DAC_OUT2") (class "Default")
      (node (ref "R30") (pin "2") (pinfunction "2_2") (pintype "passive"))
      (node (ref "U1") (pin "41") (pinfunction "PA5_41") (pintype "bidirectional"))
    )
    (net (code "36") (name "/RST") (class "Default")
      (node (ref "C15") (pin "1") (pinfunction "1_1") (pintype "passive"))
      (node (ref "P6") (pin "4") (pinfunction "4_4") (pintype "passive"))
      (node (ref "R12") (pin "1") (pinfunction "1_1") (pintype "passive"))
      (node (ref "S2") (pin "2") (pinfunction "2_2") (pintype "passive"))
      (node (ref "U1") (pin "25") (pinfunction "NRST_25") (pintype "bidirectional"))
    )
    (net (code "37") (name "/SWCLK") (class "Default")
      (node (ref "P6") (pin "3") (pinfunction "3_3") (pintype "passive"))
      (node (ref "U1") (pin "109") (pinfunction "PA14(JTCK-SWCLK)_109") (pintype "bidirectional"))
    )
    (net (code "38") (name "/SWDIO") (class "Default")
      (node (ref "P6") (pin "2") (pinfunction "2_2") (pintype "passive"))
      (node (ref "U1") (pin "105") (pinfunction "PA13(JTMS-SWDIO)_105") (pintype "bidirectional"))
    )
    (net (code "39") (name "/TIM1_CH1") (class "Default")
      (node (ref "R57") (pin "1") (pinfunction "1_1") (pintype "passive"))
      (node (ref "U1") (pin "60") (pinfunction "PE9_60") (pintype "bidirectional"))
    )
    (net (code "40") (name "/TIM1_CH2") (class "Default")
      (node (ref "R58") (pin "1") (pinfunction "1_1") (pintype "passive"))
      (node (ref "U1") (pin "64") (pinfunction "PE11_64") (pintype "bidirectional"))
    )
    (net (code "41") (name "/TIM1_CH3") (class "Default")
      (node (ref "R59") (pin "1") (pinfunction "1_1") (pintype "passive"))
      (node (ref "U1") (pin "66") (pinfunction "PE13_66") (pintype "bidirectional"))
    )
    (net (code "42") (name "/TIM1_CH4") (class "Default")
      (node (ref "R60") (pin "1") (pinfunction "1_1") (pintype "passive"))
      (node (ref "U1") (pin "67") (pinfunction "PE14_67") (pintype "bidirectional"))
    )
    (net (code "43") (name "/TIM2_CH1") (class "Default")
      (node (ref "R49") (pin "1") (pinfunction "1_1") (pintype "passive"))
      (node (ref "U1") (pin "110") (pinfunction "PA15(JTDI)_110") (pintype "bidirectional"))
    )
    (net (code "44") (name "/TIM2_CH2") (class "Default")
      (node (ref "R50") (pin "1") (pinfunction "1_1") (pintype "passive"))
      (node (ref "U1") (pin "133") (pinfunction "PB3(JTDO/TRACESWO)_133") (pintype "bidirectional"))
    )
    (net (code "45") (name "/TIM2_CH3") (class "Default")
      (node (ref "R51") (pin "1") (pinfunction "1_1") (pintype "passive"))
      (node (ref "U1") (pin "69") (pinfunction "PB10_69") (pintype "bidirectional"))
    )
    (net (code "46") (name "/TIM2_CH4") (class "Default")
      (node (ref "R52") (pin "1") (pinfunction "1_1") (pintype "passive"))
      (node (ref "U1") (pin "70") (pinfunction "PB11_70") (pintype "bidirectional"))
    )
    (net (code "47") (name "/TIM3_CH1") (class "Default")
      (node (ref "R53") (pin "1") (pinfunction "1_1") (pintype "passive"))
      (node (ref "U1") (pin "96") (pinfunction "PC6_96") (pintype "bidirectional"))
    )
    (net (code "48") (name "/TIM3_CH2") (class "Default")
      (node (ref "R54") (pin "1") (pinfunction "1_1") (pintype "passive"))
      (node (ref "U1") (pin "97") (pinfunction "PC7_97") (pintype "bidirectional"))
    )
    (net (code "49") (name "/TIM3_CH3") (class "Default")
      (node (ref "R55") (pin "1") (pinfunction "1_1") (pintype "passive"))
      (node (ref "U1") (pin "98") (pinfunction "PC8_98") (pintype "bidirectional"))
    )
    (net (code "50") (name "/TIM3_CH4") (class "Default")
      (node (ref "R56") (pin "1") (pinfunction "1_1") (pintype "passive"))
      (node (ref "U1") (pin "99") (pinfunction "PC9_99") (pintype "bidirectional"))
    )
    (net (code "51") (name "/TIM4_CH1") (class "Default")
      (node (ref "R61") (pin "1") (pinfunction "1_1") (pintype "passive"))
      (node (ref "U1") (pin "81") (pinfunction "PD12_81") (pintype "bidirectional"))
    )
    (net (code "52") (name "/TIM4_CH2") (class "Default")
      (node (ref "R62") (pin "1") (pinfunction "1_1") (pintype "passive"))
      (node (ref "U1") (pin "82") (pinfunction "PD13_82") (pintype "bidirectional"))
    )
    (net (code "53") (name "/TIM4_CH3") (class "Default")
      (node (ref "R63") (pin "1") (pinfunction "1_1") (pintype "passive"))
      (node (ref "U1") (pin "85") (pinfunction "PD14_85") (pintype "bidirectional"))
    )
    (net (code "54") (name "/TIM4_CH4") (class "Default")
      (node (ref "R64") (pin "1") (pinfunction "1_1") (pintype "passive"))
      (node (ref "U1") (pin "86") (pinfunction "PD15_86") (pintype "bidirectional"))
    )
    (net (code "55") (name "/UART4_RX") (class "Default")
      (node (ref "P4") (pin "2") (pinfunction "2_2") (pintype "passive"))
      (node (ref "U1") (pin "112") (pinfunction "PC11_112") (pintype "bidirectional"))
    )
    (net (code "56") (name "/UART4_TX") (class "Default")
      (node (ref "P4") (pin "3") (pinfunction "3_3") (pintype "passive"))
      (node (ref "U1") (pin "111") (pinfunction "PC10_111") (pintype "bidirectional"))
    )
    (net (code "57") (name "/UART5_RX") (class "Default")
      (node (ref "P5") (pin "2") (pinfunction "2_2") (pintype "passive"))
      (node (ref "U1") (pin "116") (pinfunction "PD2_116") (pintype "bidirectional"))
    )
    (net (code "58") (name "/UART5_TX") (class "Default")
      (node (ref "P5") (pin "3") (pinfunction "3_3") (pintype "passive"))
      (node (ref "U1") (pin "113") (pinfunction "PC12_113") (pintype "bidirectional"))
    )
    (net (code "59") (name "/UART7_RX") (class "Default")
      (node (ref "D8") (pin "2") (pinfunction "K_2") (pintype "passive"))
      (node (ref "J1") (pin "8") (pinfunction "8_8") (pintype "passive"))
      (node (ref "J2") (pin "2") (pinfunction "2_2") (pintype "passive"))
      (node (ref "U1") (pin "58") (pinfunction "PE7_58") (pintype "bidirectional"))
    )
    (net (code "60") (name "/UART7_TX") (class "Default")
      (node (ref "D9") (pin "2") (pinfunction "K_2") (pintype "passive"))
      (node (ref "J1") (pin "10") (pinfunction "10_10") (pintype "passive"))
      (node (ref "J2") (pin "3") (pinfunction "3_3") (pintype "passive"))
      (node (ref "U1") (pin "59") (pinfunction "PE8_59") (pintype "bidirectional"))
    )
    (net (code "61") (name "/USART1_RX") (class "Default")
      (node (ref "D6") (pin "2") (pinfunction "K_2") (pintype "passive"))
      (node (ref "P1") (pin "2") (pinfunction "2_2") (pintype "passive"))
      (node (ref "U1") (pin "102") (pinfunction "PA10_102") (pintype "bidirectional"))
    )
    (net (code "62") (name "/USART1_TX") (class "Default")
      (node (ref "D7") (pin "2") (pinfunction "K_2") (pintype "passive"))
      (node (ref "P1") (pin "3") (pinfunction "3_3") (pintype "passive"))
      (node (ref "U1") (pin "101") (pinfunction "PA9_101") (pintype "bidirectional"))
    )
    (net (code "63") (name "/USART2_RX") (class "Default")
      (node (ref "P2") (pin "2") (pinfunction "2_2") (pintype "passive"))
      (node (ref "U1") (pin "122") (pinfunction "PD6_122") (pintype "bidirectional"))
    )
    (net (code "64") (name "/USART2_TX") (class "Default")
      (node (ref "P2") (pin "3") (pinfunction "3_3") (pintype "passive"))
      (node (ref "U1") (pin "119") (pinfunction "PD5_119") (pintype "bidirectional"))
    )
    (net (code "65") (name "/USART3_CK") (class "Default")
      (node (ref "P3") (pin "4") (pinfunction "4_4") (pintype "passive"))
      (node (ref "U1") (pin "79") (pinfunction "PD10_79") (pintype "bidirectional"))
    )
    (net (code "66") (name "/USART3_RX") (class "Default")
      (node (ref "P3") (pin "2") (pinfunction "2_2") (pintype "passive"))
      (node (ref "U1") (pin "78") (pinfunction "PD9_78") (pintype "bidirectional"))
    )
    (net (code "67") (name "/USART3_TX") (class "Default")
      (node (ref "P3") (pin "3") (pinfunction "3_3") (pintype "passive"))
      (node (ref "U1") (pin "77") (pinfunction "PD8_77") (pintype "bidirectional"))
    )
    (net (code "68") (name "GND") (class "Default")
      (node (ref "C1") (pin "2") (pinfunction "2_2") (pintype "passive"))
      (node (ref "C10") (pin "1") (pinfunction "1_1") (pintype "passive"))
      (node (ref "C11") (pin "2") (pinfunction "2_2") (pintype "passive"))
      (node (ref "C12") (pin "1") (pinfunction "1_1") (pintype "passive"))
      (node (ref "C14") (pin "1") (pinfunction "1_1") (pintype "passive"))
      (node (ref "C15") (pin "2") (pinfunction "2_2") (pintype "passive"))
      (node (ref "C18") (pin "1") (pinfunction "1_1") (pintype "passive"))
      (node (ref "C19") (pin "2") (pinfunction "2_2") (pintype "passive"))
      (node (ref "C2") (pin "1") (pinfunction "1_1") (pintype "passive"))
      (node (ref "C20") (pin "2") (pinfunction "2_2") (pintype "passive"))
      (node (ref "C21") (pin "1") (pinfunction "1_1") (pintype "passive"))
      (node (ref "C22") (pin "1") (pinfunction "1_1") (pintype "passive"))
      (node (ref "C23") (pin "1") (pinfunction "1_1") (pintype "passive"))
      (node (ref "C24") (pin "1") (pinfunction "1_1") (pintype "passive"))
      (node (ref "C25") (pin "2") (pinfunction "2_2") (pintype "passive"))
      (node (ref "C26") (pin "2") (pinfunction "2_2") (pintype "passive"))
      (node (ref "C27") (pin "1") (pinfunction "1_1") (pintype "passive"))
      (node (ref "C28") (pin "1") (pinfunction "1_1") (pintype "passive"))
      (node (ref "C29") (pin "1") (pinfunction "1_1") (pintype "passive"))
      (node (ref "C3") (pin "2") (pinfunction "2_2") (pintype "passive"))
      (node (ref "C30") (pin "1") (pinfunction "1_1") (pintype "passive"))
      (node (ref "C31") (pin "1") (pinfunction "1_1") (pintype "passive"))
      (node (ref "C32") (pin "1") (pinfunction "1_1") (pintype "passive"))
      (node (ref "C33") (pin "1") (pinfunction "1_1") (pintype "passive"))
      (node (ref "C34") (pin "1") (pinfunction "1_1") (pintype "passive"))
      (node (ref "C35") (pin "1") (pinfunction "1_1") (pintype "passive"))
      (node (ref "C36") (pin "1") (pinfunction "1_1") (pintype "passive"))
      (node (ref "C37") (pin "1") (pinfunction "1_1") (pintype "passive"))
      (node (ref "C38") (pin "1") (pinfunction "1_1") (pintype "passive"))
      (node (ref "C4") (pin "2") (pinfunction "2_2") (pintype "passive"))
      (node (ref "C5") (pin "2") (pinfunction "2_2") (pintype "passive"))
      (node (ref "C6") (pin "1") (pinfunction "1_1") (pintype "passive"))
      (node (ref "C7") (pin "2") (pinfunction "2_2") (pintype "passive"))
      (node (ref "C8") (pin "2") (pinfunction "2_2") (pintype "passive"))
      (node (ref "C9") (pin "2") (pinfunction "2_2") (pintype "passive"))
      (node (ref "D1") (pin "1") (pinfunction "A_1") (pintype "passive"))
      (node (ref "D2") (pin "2") (pinfunction "K_2") (pintype "passive"))
      (node (ref "D3") (pin "1") (pinfunction "A_1") (pintype "passive"))
      (node (ref "D4") (pin "2") (pinfunction "K_2") (pintype "passive"))
      (node (ref "D5") (pin "2") (pinfunction "K_2") (pintype "passive"))
      (node (ref "J1") (pin "6") (pinfunction "6_6") (pintype "passive"))
      (node (ref "J2") (pin "4") (pinfunction "4_4") (pintype "passive"))
      (node (ref "P1") (pin "4") (pinfunction "4_4") (pintype "passive"))
      (node (ref "P14") (pin "1") (pinfunction "1_1") (pintype "passive"))
      (node (ref "P14") (pin "2") (pinfunction "2_2") (pintype "passive"))
      (node (ref "P15") (pin "16") (pinfunction "16_16") (pintype "passive"))
      (node (ref "P17") (pin "10") (pinfunction "10_10") (pintype "passive"))
      (node (ref "P17") (pin "12") (pinfunction "12_12") (pintype "passive"))
      (node (ref "P17") (pin "14") (pinfunction "14_14") (pintype "passive"))
      (node (ref "P17") (pin "16") (pinfunction "16_16") (pintype "passive"))
      (node (ref "P17") (pin "2") (pinfunction "2_2") (pintype "passive"))
      (node (ref "P17") (pin "4") (pinfunction "4_4") (pintype "passive"))
      (node (ref "P17") (pin "6") (pinfunction "6_6") (pintype "passive"))
      (node (ref "P17") (pin "8") (pinfunction "8_8") (pintype "passive"))
      (node (ref "P19") (pin "10") (pinfunction "10_10") (pintype "passive"))
      (node (ref "P19") (pin "12") (pinfunction "12_12") (pintype "passive"))
      (node (ref "P19") (pin "14") (pinfunction "14_14") (pintype "passive"))
      (node (ref "P19") (pin "16") (pinfunction "16_16") (pintype "passive"))
      (node (ref "P19") (pin "2") (pinfunction "2_2") (pintype "passive"))
      (node (ref "P19") (pin "4") (pinfunction "4_4") (pintype "passive"))
      (node (ref "P19") (pin "6") (pinfunction "6_6") (pintype "passive"))
      (node (ref "P19") (pin "8") (pinfunction "8_8") (pintype "passive"))
      (node (ref "P2") (pin "4") (pinfunction "4_4") (pintype "passive"))
      (node (ref "P3") (pin "5") (pinfunction "5_5") (pintype "passive"))
      (node (ref "P4") (pin "4") (pinfunction "4_4") (pintype "passive"))
      (node (ref "P5") (pin "4") (pinfunction "4_4") (pintype "passive"))
      (node (ref "P6") (pin "5") (pinfunction "5_5") (pintype "passive"))
      (node (ref "R11") (pin "2") (pinfunction "2_2") (pintype "passive"))
      (node (ref "R16") (pin "1") (pinfunction "1_1") (pintype "passive"))
      (node (ref "R17") (pin "1") (pinfunction "1_1") (pintype "passive"))
      (node (ref "R19") (pin "1") (pinfunction "1_1") (pintype "passive"))
      (node (ref "R2") (pin "1") (pinfunction "1_1") (pintype "passive"))
      (node (ref "R6") (pin "1") (pinfunction "1_1") (pintype "passive"))
      (node (ref "S2") (pin "1") (pinfunction "1_1") (pintype "passive"))
      (node (ref "U1") (pin "107") (pinfunction "VSS_107") (pintype "power_in"))
      (node (ref "U1") (pin "120") (pinfunction "VSS_120") (pintype "power_in"))
      (node (ref "U1") (pin "130") (pinfunction "VSS_130") (pintype "power_in"))
      (node (ref "U1") (pin "16") (pinfunction "VSS_16") (pintype "power_in"))
      (node (ref "U1") (pin "38") (pinfunction "VSS_38") (pintype "power_in"))
      (node (ref "U1") (pin "51") (pinfunction "VSS_51") (pintype "power_in"))
      (node (ref "U1") (pin "61") (pinfunction "VSS_61") (pintype "power_in"))
      (node (ref "U1") (pin "83") (pinfunction "VSS_83") (pintype "power_in"))
      (node (ref "U1") (pin "94") (pinfunction "VSS_94") (pintype "power_in"))
      (node (ref "U2") (pin "3") (pinfunction "COMMON_3") (pintype "power_in"))
      (node (ref "U2") (pin "5") (pinfunction "ON/OFF_5") (pintype "passive"))
      (node (ref "U3") (pin "3") (pinfunction "COMMON_3") (pintype "power_in"))
      (node (ref "U3") (pin "5") (pinfunction "ON/OFF_5") (pintype "passive"))
      (node (ref "U4") (pin "1") (pinfunction "GND_1") (pintype "passive"))
      (node (ref "U5") (pin "2") (pinfunction "VSS_2") (pintype "passive"))
      (node (ref "U5") (pin "8") (pinfunction "STBY_8") (pintype "passive"))
      (node (ref "U6") (pin "2") (pinfunction "VSS_2") (pintype "passive"))
      (node (ref "U6") (pin "8") (pinfunction "STBY_8") (pintype "passive"))
      (node (ref "X1") (pin "2") (pinfunction "2_2") (pintype "passive"))
      (node (ref "X2") (pin "2") (pinfunction "2_2") (pintype "passive"))
      (node (ref "X3") (pin "2") (pinfunction "2_2") (pintype "passive"))
      (node (ref "X4") (pin "2") (pinfunction "2_2") (pintype "passive"))
      (node (ref "X5") (pin "2") (pinfunction "2_2") (pintype "passive"))
      (node (ref "X6") (pin "2") (pinfunction "2_2") (pintype "passive"))
      (node (ref "X7") (pin "2") (pinfunction "2_2") (pintype "passive"))
      (node (ref "X8") (pin "2") (pinfunction "2_2") (pintype "passive"))
    )
    (net (code "69") (name "Net-(D1-K)") (class "Default")
      (node (ref "D1") (pin "2") (pinfunction "K_2") (pintype "passive"))
      (node (ref "L1") (pin "1") (pinfunction "1_1") (pintype "passive"))
      (node (ref "U2") (pin "2") (pinfunction "OUT_2") (pintype "passive"))
    )
    (net (code "70") (name "Net-(D2-A)") (class "Default")
      (node (ref "D2") (pin "1") (pinfunction "A_1") (pintype "passive"))
      (node (ref "R3") (pin "2") (pinfunction "2_2") (pintype "passive"))
    )
    (net (code "71") (name "Net-(D3-K)") (class "Default")
      (node (ref "D3") (pin "2") (pinfunction "K_2") (pintype "passive"))
      (node (ref "L2") (pin "1") (pinfunction "1_1") (pintype "passive"))
      (node (ref "U3") (pin "2") (pinfunction "OUT_2") (pintype "passive"))
    )
    (net (code "72") (name "Net-(D4-A)") (class "Default")
      (node (ref "D4") (pin "1") (pinfunction "A_1") (pintype "passive"))
      (node (ref "R7") (pin "2") (pinfunction "2_2") (pintype "passive"))
    )
    (net (code "73") (name "Net-(D5-A)") (class "Default")
      (node (ref "D5") (pin "1") (pinfunction "A_1") (pintype "passive"))
      (node (ref "R65") (pin "1") (pinfunction "1_1") (pintype "passive"))
    )
    (net (code "74") (name "Net-(D6-A)") (class "Default")
      (node (ref "D6") (pin "1") (pinfunction "A_1") (pintype "passive"))
      (node (ref "R66") (pin "1") (pinfunction "1_1") (pintype "passive"))
    )
    (net (code "75") (name "Net-(D7-A)") (class "Default")
      (node (ref "D7") (pin "1") (pinfunction "A_1") (pintype "passive"))
      (node (ref "R67") (pin "1") (pinfunction "1_1") (pintype "passive"))
    )
    (net (code "76") (name "Net-(D8-A)") (class "Default")
      (node (ref "D8") (pin "1") (pinfunction "A_1") (pintype "passive"))
      (node (ref "R68") (pin "1") (pinfunction "1_1") (pintype "passive"))
    )
    (net (code "77") (name "Net-(D9-A)") (class "Default")
      (node (ref "D9") (pin "1") (pinfunction "A_1") (pintype "passive"))
      (node (ref "R69") (pin "1") (pinfunction "1_1") (pintype "passive"))
    )
    (net (code "78") (name "Net-(P14-Pad5)") (class "Default")
      (node (ref "P14") (pin "5") (pinfunction "5_5") (pintype "passive"))
      (node (ref "R25") (pin "2") (pinfunction "2_2") (pintype "passive"))
    )
    (net (code "79") (name "Net-(P14-Pad6)") (class "Default")
      (node (ref "P14") (pin "6") (pinfunction "6_6") (pintype "passive"))
      (node (ref "R26") (pin "1") (pinfunction "1_1") (pintype "passive"))
    )
    (net (code "80") (name "Net-(P14-Pad7)") (class "Default")
      (node (ref "P14") (pin "7") (pinfunction "7_7") (pintype "passive"))
      (node (ref "R27") (pin "2") (pinfunction "2_2") (pintype "passive"))
    )
    (net (code "81") (name "Net-(P14-Pad8)") (class "Default")
      (node (ref "P14") (pin "8") (pinfunction "8_8") (pintype "passive"))
      (node (ref "R28") (pin "1") (pinfunction "1_1") (pintype "passive"))
    )
    (net (code "82") (name "Net-(P14-Pad9)") (class "Default")
      (node (ref "P14") (pin "9") (pinfunction "9_9") (pintype "passive"))
      (node (ref "R29") (pin "2") (pinfunction "2_2") (pintype "passive"))
    )
    (net (code "83") (name "Net-(P14-Pad10)") (class "Default")
      (node (ref "P14") (pin "10") (pinfunction "10_10") (pintype "passive"))
      (node (ref "R30") (pin "1") (pinfunction "1_1") (pintype "passive"))
    )
    (net (code "84") (name "Net-(P14-Pad11)") (class "Default")
      (node (ref "P14") (pin "11") (pinfunction "11_11") (pintype "passive"))
      (node (ref "R31") (pin "2") (pinfunction "2_2") (pintype "passive"))
    )
    (net (code "85") (name "Net-(P14-Pad12)") (class "Default")
      (node (ref "P14") (pin "12") (pinfunction "12_12") (pintype "passive"))
      (node (ref "R32") (pin "1") (pinfunction "1_1") (pintype "passive"))
    )
    (net (code "86") (name "Net-(P14-Pad13)") (class "Default")
      (node (ref "P14") (pin "13") (pinfunction "13_13") (pintype "passive"))
      (node (ref "R33") (pin "2") (pinfunction "2_2") (pintype "passive"))
    )
    (net (code "87") (name "Net-(P14-Pad14)") (class "Default")
      (node (ref "P14") (pin "14") (pinfunction "14_14") (pintype "passive"))
      (node (ref "R34") (pin "1") (pinfunction "1_1") (pintype "passive"))
    )
    (net (code "88") (name "Net-(P15-Pad1)") (class "Default")
      (node (ref "P15") (pin "1") (pinfunction "1_1") (pintype "passive"))
      (node (ref "R35") (pin "2") (pinfunction "2_2") (pintype "passive"))
    )
    (net (code "89") (name "Net-(P15-Pad2)") (class "Default")
      (node (ref "P15") (pin "2") (pinfunction "2_2") (pintype "passive"))
      (node (ref "R36") (pin "1") (pinfunction "1_1") (pintype "passive"))
    )
    (net (code "90") (name "Net-(P15-Pad3)") (class "Default")
      (node (ref "P15") (pin "3") (pinfunction "3_3") (pintype "passive"))
      (node (ref "R37") (pin "2") (pinfunction "2_2") (pintype "passive"))
    )
    (net (code "91") (name "Net-(P15-Pad4)") (class "Default")
      (node (ref "P15") (pin "4") (pinfunction "4_4") (pintype "passive"))
      (node (ref "R38") (pin "1") (pinfunction "1_1") (pintype "passive"))
    )
    (net (code "92") (name "Net-(P15-Pad5)") (class "Default")
      (node (ref "P15") (pin "5") (pinfunction "5_5") (pintype "passive"))
      (node (ref "R39") (pin "2") (pinfunction "2_2") (pintype "passive"))
    )
    (net (code "93") (name "Net-(P15-Pad6)") (class "Default")
      (node (ref "P15") (pin "6") (pinfunction "6_6") (pintype "passive"))
      (node (ref "R40") (pin "1") (pinfunction "1_1") (pintype "passive"))
    )
    (net (code "94") (name "Net-(P15-Pad7)") (class "Default")
      (node (ref "P15") (pin "7") (pinfunction "7_7") (pintype "passive"))
      (node (ref "R41") (pin "2") (pinfunction "2_2") (pintype "passive"))
    )
    (net (code "95") (name "Net-(P15-Pad8)") (class "Default")
      (node (ref "P15") (pin "8") (pinfunction "8_8") (pintype "passive"))
      (node (ref "R42") (pin "1") (pinfunction "1_1") (pintype "passive"))
    )
    (net (code "96") (name "Net-(P15-Pad9)") (class "Default")
      (node (ref "P15") (pin "9") (pinfunction "9_9") (pintype "passive"))
      (node (ref "R43") (pin "2") (pinfunction "2_2") (pintype "passive"))
    )
    (net (code "97") (name "Net-(P15-Pad10)") (class "Default")
      (node (ref "P15") (pin "10") (pinfunction "10_10") (pintype "passive"))
      (node (ref "R44") (pin "1") (pinfunction "1_1") (pintype "passive"))
    )
    (net (code "98") (name "Net-(P15-Pad11)") (class "Default")
      (node (ref "P15") (pin "11") (pinfunction "11_11") (pintype "passive"))
      (node (ref "R45") (pin "2") (pinfunction "2_2") (pintype "passive"))
    )
    (net (code "99") (name "Net-(P15-Pad12)") (class "Default")
      (node (ref "P15") (pin "12") (pinfunction "12_12") (pintype "passive"))
      (node (ref "R46") (pin "1") (pinfunction "1_1") (pintype "passive"))
    )
    (net (code "100") (name "Net-(P15-Pad13)") (class "Default")
      (node (ref "P15") (pin "13") (pinfunction "13_13") (pintype "passive"))
      (node (ref "R47") (pin "2") (pinfunction "2_2") (pintype "passive"))
    )
    (net (code "101") (name "Net-(P15-Pad14)") (class "Default")
      (node (ref "P15") (pin "14") (pinfunction "14_14") (pintype "passive"))
      (node (ref "R48") (pin "1") (pinfunction "1_1") (pintype "passive"))
    )
    (net (code "102") (name "Net-(P16-Pad1)") (class "Default")
      (node (ref "P16") (pin "1") (pinfunction "1_1") (pintype "passive"))
      (node (ref "R49") (pin "2") (pinfunction "2_2") (pintype "passive"))
    )
    (net (code "103") (name "Net-(P16-Pad2)") (class "Default")
      (node (ref "P16") (pin "2") (pinfunction "2_2") (pintype "passive"))
      (node (ref "R50") (pin "2") (pinfunction "2_2") (pintype "passive"))
    )
    (net (code "104") (name "Net-(P16-Pad3)") (class "Default")
      (node (ref "P16") (pin "3") (pinfunction "3_3") (pintype "passive"))
      (node (ref "R51") (pin "2") (pinfunction "2_2") (pintype "passive"))
    )
    (net (code "105") (name "Net-(P16-Pad4)") (class "Default")
      (node (ref "P16") (pin "4") (pinfunction "4_4") (pintype "passive"))
      (node (ref "R52") (pin "2") (pinfunction "2_2") (pintype "passive"))
    )
    (net (code "106") (name "Net-(P16-Pad5)") (class "Default")
      (node (ref "P16") (pin "5") (pinfunction "5_5") (pintype "passive"))
      (node (ref "R53") (pin "2") (pinfunction "2_2") (pintype "passive"))
    )
    (net (code "107") (name "Net-(P16-Pad6)") (class "Default")
      (node (ref "P16") (pin "6") (pinfunction "6_6") (pintype "passive"))
      (node (ref "R54") (pin "2") (pinfunction "2_2") (pintype "passive"))
    )
    (net (code "108") (name "Net-(P16-Pad7)") (class "Default")
      (node (ref "P16") (pin "7") (pinfunction "7_7") (pintype "passive"))
      (node (ref "R55") (pin "2") (pinfunction "2_2") (pintype "passive"))
    )
    (net (code "109") (name "Net-(P16-Pad8)") (class "Default")
      (node (ref "P16") (pin "8") (pinfunction "8_8") (pintype "passive"))
      (node (ref "R56") (pin "2") (pinfunction "2_2") (pintype "passive"))
    )
    (net (code "110") (name "Net-(P18-Pad1)") (class "Default")
      (node (ref "P18") (pin "1") (pinfunction "1_1") (pintype "passive"))
      (node (ref "R57") (pin "2") (pinfunction "2_2") (pintype "passive"))
    )
    (net (code "111") (name "Net-(P18-Pad2)") (class "Default")
      (node (ref "P18") (pin "2") (pinfunction "2_2") (pintype "passive"))
      (node (ref "R58") (pin "2") (pinfunction "2_2") (pintype "passive"))
    )
    (net (code "112") (name "Net-(P18-Pad3)") (class "Default")
      (node (ref "P18") (pin "3") (pinfunction "3_3") (pintype "passive"))
      (node (ref "R59") (pin "2") (pinfunction "2_2") (pintype "passive"))
    )
    (net (code "113") (name "Net-(P18-Pad4)") (class "Default")
      (node (ref "P18") (pin "4") (pinfunction "4_4") (pintype "passive"))
      (node (ref "R60") (pin "2") (pinfunction "2_2") (pintype "passive"))
    )
    (net (code "114") (name "Net-(P18-Pad5)") (class "Default")
      (node (ref "P18") (pin "5") (pinfunction "5_5") (pintype "passive"))
      (node (ref "R61") (pin "2") (pinfunction "2_2") (pintype "passive"))
    )
    (net (code "115") (name "Net-(P18-Pad6)") (class "Default")
      (node (ref "P18") (pin "6") (pinfunction "6_6") (pintype "passive"))
      (node (ref "R62") (pin "2") (pinfunction "2_2") (pintype "passive"))
    )
    (net (code "116") (name "Net-(P18-Pad7)") (class "Default")
      (node (ref "P18") (pin "7") (pinfunction "7_7") (pintype "passive"))
      (node (ref "R63") (pin "2") (pinfunction "2_2") (pintype "passive"))
    )
    (net (code "117") (name "Net-(P18-Pad8)") (class "Default")
      (node (ref "P18") (pin "8") (pinfunction "8_8") (pintype "passive"))
      (node (ref "R64") (pin "2") (pinfunction "2_2") (pintype "passive"))
    )
    (net (code "118") (name "Net-(R1-A)") (class "Default")
      (node (ref "R1") (pin "1") (pinfunction "A_1") (pintype "passive"))
      (node (ref "R2") (pin "2") (pinfunction "2_2") (pintype "passive"))
      (node (ref "U2") (pin "4") (pinfunction "FB_4") (pintype "passive"))
    )
    (net (code "119") (name "Net-(R1-B)") (class "Default")
      (node (ref "C3") (pin "1") (pinfunction "1_1") (pintype "passive"))
      (node (ref "C4") (pin "1") (pinfunction "1_1") (pintype "passive"))
      (node (ref "L1") (pin "2") (pinfunction "2_2") (pintype "passive"))
      (node (ref "R1") (pin "2") (pinfunction "B_2") (pintype "passive"))
      (node (ref "R1") (pin "3") (pinfunction "TAP_3") (pintype "passive"))
      (node (ref "R3") (pin "1") (pinfunction "1_1") (pintype "passive"))
      (node (ref "R4") (pin "1") (pinfunction "1_1") (pintype "passive"))
    )
    (net (code "120") (name "Net-(R5-A)") (class "Default")
      (node (ref "R5") (pin "1") (pinfunction "A_1") (pintype "passive"))
      (node (ref "R6") (pin "2") (pinfunction "2_2") (pintype "passive"))
      (node (ref "U3") (pin "4") (pinfunction "FB_4") (pintype "passive"))
    )
    (net (code "121") (name "Net-(R5-B)") (class "Default")
      (node (ref "C7") (pin "1") (pinfunction "1_1") (pintype "passive"))
      (node (ref "C8") (pin "1") (pinfunction "1_1") (pintype "passive"))
      (node (ref "L2") (pin "2") (pinfunction "2_2") (pintype "passive"))
      (node (ref "R5") (pin "2") (pinfunction "B_2") (pintype "passive"))
      (node (ref "R5") (pin "3") (pinfunction "TAP_3") (pintype "passive"))
      (node (ref "R7") (pin "1") (pinfunction "1_1") (pintype "passive"))
      (node (ref "R8") (pin "1") (pinfunction "1_1") (pintype "passive"))
    )
    (net (code "122") (name "Net-(U1A-PC14-OSC32_IN(PC14))") (class "Default")
      (node (ref "C23") (pin "2") (pinfunction "2_2") (pintype "passive"))
      (node (ref "U1") (pin "8") (pinfunction "PC14-OSC32_IN(PC14)_8") (pintype "bidirectional"))
      (node (ref "Y2") (pin "2") (pinfunction "2_2") (pintype "passive"))
    )
    (net (code "123") (name "Net-(U1A-PC15-OSC32_OUT(PC15))") (class "Default")
      (node (ref "C24") (pin "2") (pinfunction "2_2") (pintype "passive"))
      (node (ref "U1") (pin "9") (pinfunction "PC15-OSC32_OUT(PC15)_9") (pintype "bidirectional"))
      (node (ref "Y2") (pin "1") (pinfunction "1_1") (pintype "passive"))
    )
    (net (code "124") (name "Net-(U1B-PH0-OSC_IN(PH0))") (class "Default")
      (node (ref "C19") (pin "1") (pinfunction "1_1") (pintype "passive"))
      (node (ref "R20") (pin "2") (pinfunction "2_2") (pintype "passive"))
      (node (ref "U1") (pin "23") (pinfunction "PH0-OSC_IN(PH0)_23") (pintype "bidirectional"))
      (node (ref "Y1") (pin "1") (pinfunction "1_1") (pintype "passive"))
    )
    (net (code "125") (name "Net-(U1B-PH1-OSC_OUT(PH1))") (class "Default")
      (node (ref "C20") (pin "1") (pinfunction "1_1") (pintype "passive"))
      (node (ref "R20") (pin "1") (pinfunction "1_1") (pintype "passive"))
      (node (ref "U1") (pin "24") (pinfunction "PH1-OSC_OUT(PH1)_24") (pintype "bidirectional"))
      (node (ref "Y1") (pin "2") (pinfunction "2_2") (pintype "passive"))
    )
    (net (code "126") (name "Net-(U1B-VCAP_1)") (class "Default")
      (node (ref "C22") (pin "2") (pinfunction "2_2") (pintype "passive"))
      (node (ref "U1") (pin "71") (pinfunction "VCAP_1_71") (pintype "power_in"))
    )
    (net (code "127") (name "Net-(U1B-VCAP_2)") (class "Default")
      (node (ref "C21") (pin "2") (pinfunction "2_2") (pintype "passive"))
      (node (ref "U1") (pin "106") (pinfunction "VCAP_2_106") (pintype "power_in"))
    )
    (net (code "128") (name "Net-(U4-OUT)") (class "Default")
      (node (ref "C11") (pin "1") (pinfunction "1_1") (pintype "passive"))
      (node (ref "C12") (pin "2") (pinfunction "2_2") (pintype "passive"))
      (node (ref "R65") (pin "2") (pinfunction "2_2") (pintype "passive"))
      (node (ref "R9") (pin "1") (pinfunction "1_1") (pintype "passive"))
      (node (ref "U4") (pin "2") (pinfunction "OUT_2") (pintype "passive"))
    )
    (net (code "129") (name "VCC_5V") (class "Default")
      (node (ref "C10") (pin "2") (pinfunction "2_2") (pintype "passive"))
      (node (ref "C25") (pin "1") (pinfunction "1_1") (pintype "passive"))
      (node (ref "C26") (pin "1") (pinfunction "1_1") (pintype "passive"))
      (node (ref "C9") (pin "1") (pinfunction "1_1") (pintype "passive"))
      (node (ref "J1") (pin "2") (pinfunction "2_2") (pintype "passive"))
      (node (ref "J2") (pin "1") (pinfunction "1_1") (pintype "passive"))
      (node (ref "P1") (pin "1") (pinfunction "1_1") (pintype "passive"))
      (node (ref "P14") (pin "4") (pinfunction "4_4") (pintype "passive"))
      (node (ref "P15") (pin "15") (pinfunction "15_15") (pintype "passive"))
      (node (ref "P19") (pin "1") (pinfunction "1_1") (pintype "passive"))
      (node (ref "P19") (pin "11") (pinfunction "11_11") (pintype "passive"))
      (node (ref "P19") (pin "13") (pinfunction "13_13") (pintype "passive"))
      (node (ref "P19") (pin "15") (pinfunction "15_15") (pintype "passive"))
      (node (ref "P19") (pin "3") (pinfunction "3_3") (pintype "passive"))
      (node (ref "P19") (pin "5") (pinfunction "5_5") (pintype "passive"))
      (node (ref "P19") (pin "7") (pinfunction "7_7") (pintype "passive"))
      (node (ref "P19") (pin "9") (pinfunction "9_9") (pintype "passive"))
      (node (ref "P2") (pin "1") (pinfunction "1_1") (pintype "passive"))
      (node (ref "P3") (pin "1") (pinfunction "1_1") (pintype "passive"))
      (node (ref "P4") (pin "1") (pinfunction "1_1") (pintype "passive"))
      (node (ref "P5") (pin "1") (pinfunction "1_1") (pintype "passive"))
      (node (ref "P6") (pin "1") (pinfunction "1_1") (pintype "passive"))
      (node (ref "R4") (pin "2") (pinfunction "2_2") (pintype "passive"))
      (node (ref "R66") (pin "2") (pinfunction "2_2") (pintype "passive"))
      (node (ref "R67") (pin "2") (pinfunction "2_2") (pintype "passive"))
      (node (ref "R68") (pin "2") (pinfunction "2_2") (pintype "passive"))
      (node (ref "R69") (pin "2") (pinfunction "2_2") (pintype "passive"))
      (node (ref "U4") (pin "3") (pinfunction "VCC_3") (pintype "passive"))
      (node (ref "U5") (pin "3") (pinfunction "VDD_3") (pintype "passive"))
      (node (ref "U6") (pin "3") (pinfunction "VDD_3") (pintype "passive"))
      (node (ref "X8") (pin "1") (pinfunction "1_1") (pintype "passive"))
    )
    (net (code "130") (name "VCC_24V") (class "Default")
      (node (ref "C1") (pin "1") (pinfunction "1_1") (pintype "passive"))
      (node (ref "C17") (pin "2") (pinfunction "2_2") (pintype "passive"))
      (node (ref "C2") (pin "2") (pinfunction "2_2") (pintype "passive"))
      (node (ref "C5") (pin "1") (pinfunction "1_1") (pintype "passive"))
      (node (ref "C6") (pin "2") (pinfunction "2_2") (pintype "passive"))
      (node (ref "R18") (pin "2") (pinfunction "2_2") (pintype "passive"))
      (node (ref "U2") (pin "1") (pinfunction "VIN_1") (pintype "passive"))
      (node (ref "U3") (pin "1") (pinfunction "VIN_1") (pintype "passive"))
      (node (ref "X1") (pin "1") (pinfunction "1_1") (pintype "passive"))
      (node (ref "X2") (pin "1") (pinfunction "1_1") (pintype "passive"))
      (node (ref "X3") (pin "1") (pinfunction "1_1") (pintype "passive"))
      (node (ref "X4") (pin "1") (pinfunction "1_1") (pintype "passive"))
      (node (ref "X5") (pin "1") (pinfunction "1_1") (pintype "passive"))
      (node (ref "X6") (pin "1") (pinfunction "1_1") (pintype "passive"))
    )
    (net (code "131") (name "VCC_ADJ") (class "Default")
      (node (ref "P17") (pin "1") (pinfunction "1_1") (pintype "passive"))
      (node (ref "P17") (pin "11") (pinfunction "11_11") (pintype "passive"))
      (node (ref "P17") (pin "13") (pinfunction "13_13") (pintype "passive"))
      (node (ref "P17") (pin "15") (pinfunction "15_15") (pintype "passive"))
      (node (ref "P17") (pin "3") (pinfunction "3_3") (pintype "passive"))
      (node (ref "P17") (pin "5") (pinfunction "5_5") (pintype "passive"))
      (node (ref "P17") (pin "7") (pinfunction "7_7") (pintype "passive"))
      (node (ref "P17") (pin "9") (pinfunction "9_9") (pintype "passive"))
      (node (ref "R8") (pin "2") (pinfunction "2_2") (pintype "passive"))
      (node (ref "X7") (pin "1") (pinfunction "1_1") (pintype "passive"))
    )
    (net (code "132") (name "VDDA") (class "Default")
      (node (ref "C13") (pin "2") (pinfunction "2_2") (pintype "passive"))
      (node (ref "R10") (pin "1") (pinfunction "1_1") (pintype "passive"))
      (node (ref "U1") (pin "32") (pinfunction "VREF+_32") (pintype "power_in"))
      (node (ref "U1") (pin "33") (pinfunction "VDDA_33") (pintype "power_in"))
    )
    (net (code "133") (name "VDD_3V3") (class "Default")
      (node (ref "C14") (pin "2") (pinfunction "2_2") (pintype "passive"))
      (node (ref "C27") (pin "2") (pinfunction "2_2") (pintype "passive"))
      (node (ref "C28") (pin "2") (pinfunction "2_2") (pintype "passive"))
      (node (ref "C29") (pin "2") (pinfunction "2_2") (pintype "passive"))
      (node (ref "C30") (pin "2") (pinfunction "2_2") (pintype "passive"))
      (node (ref "C31") (pin "2") (pinfunction "2_2") (pintype "passive"))
      (node (ref "C32") (pin "2") (pinfunction "2_2") (pintype "passive"))
      (node (ref "C33") (pin "2") (pinfunction "2_2") (pintype "passive"))
      (node (ref "C34") (pin "2") (pinfunction "2_2") (pintype "passive"))
      (node (ref "C35") (pin "2") (pinfunction "2_2") (pintype "passive"))
      (node (ref "C36") (pin "2") (pinfunction "2_2") (pintype "passive"))
      (node (ref "C37") (pin "2") (pinfunction "2_2") (pintype "passive"))
      (node (ref "C38") (pin "2") (pinfunction "2_2") (pintype "passive"))
      (node (ref "P14") (pin "3") (pinfunction "3_3") (pintype "passive"))
      (node (ref "R10") (pin "2") (pinfunction "2_2") (pintype "passive"))
      (node (ref "R12") (pin "2") (pinfunction "2_2") (pintype "passive"))
      (node (ref "R9") (pin "2") (pinfunction "2_2") (pintype "passive"))
      (node (ref "S1") (pin "1") (pinfunction "A1_1") (pintype "passive"))
      (node (ref "S1") (pin "2") (pinfunction "A2_2") (pintype "passive"))
      (node (ref "U1") (pin "108") (pinfunction "VDD_108") (pintype "power_in"))
      (node (ref "U1") (pin "121") (pinfunction "VDD_121") (pintype "power_in"))
      (node (ref "U1") (pin "131") (pinfunction "VDD_131") (pintype "power_in"))
      (node (ref "U1") (pin "143") (pinfunction "PDR_ON_143") (pintype "input"))
      (node (ref "U1") (pin "144") (pinfunction "VDD_144") (pintype "power_in"))
      (node (ref "U1") (pin "17") (pinfunction "VDD_17") (pintype "power_in"))
      (node (ref "U1") (pin "30") (pinfunction "VDD_30") (pintype "power_in"))
      (node (ref "U1") (pin "39") (pinfunction "VDD_39") (pintype "power_in"))
      (node (ref "U1") (pin "52") (pinfunction "VDD_52") (pintype "power_in"))
      (node (ref "U1") (pin "6") (pinfunction "VBAT_6") (pintype "power_in"))
      (node (ref "U1") (pin "62") (pinfunction "VDD_62") (pintype "power_in"))
      (node (ref "U1") (pin "72") (pinfunction "VDD_72") (pintype "power_in"))
      (node (ref "U1") (pin "84") (pinfunction "VDD_84") (pintype "power_in"))
      (node (ref "U1") (pin "95") (pinfunction "VDD_95") (pintype "power_in"))
      (node (ref "U5") (pin "5") (pinfunction "VIO_5") (pintype "passive"))
      (node (ref "U6") (pin "5") (pinfunction "VIO_5") (pintype "passive"))
    )
    (net (code "134") (name "VSSA") (class "Default")
      (node (ref "C13") (pin "1") (pinfunction "1_1") (pintype "passive"))
      (node (ref "R11") (pin "1") (pinfunction "1_1") (pintype "passive"))
      (node (ref "U1") (pin "31") (pinfunction "VSSA_31") (pintype "power_in"))
    )
    (net (code "135") (name "unconnected-(J1-Pad1)") (class "Default")
      (node (ref "J1") (pin "1") (pinfunction "1_1") (pintype "passive"))
    )
    (net (code "136") (name "unconnected-(J1-Pad3)") (class "Default")
      (node (ref "J1") (pin "3") (pinfunction "3_3") (pintype "passive"))
    )
    (net (code "137") (name "unconnected-(J1-Pad4)") (class "Default")
      (node (ref "J1") (pin "4") (pinfunction "4_4") (pintype "passive"))
    )
    (net (code "138") (name "unconnected-(J1-Pad5)") (class "Default")
      (node (ref "J1") (pin "5") (pinfunction "5_5") (pintype "passive"))
    )
    (net (code "139") (name "unconnected-(J1-Pad7)") (class "Default")
      (node (ref "J1") (pin "7") (pinfunction "7_7") (pintype "passive"))
    )
    (net (code "140") (name "unconnected-(J1-Pad9)") (class "Default")
      (node (ref "J1") (pin "9") (pinfunction "9_9") (pintype "passive"))
    )
    (net (code "141") (name "unconnected-(J1-Pad11)") (class "Default")
      (node (ref "J1") (pin "11") (pinfunction "11_11") (pintype "passive"))
    )
    (net (code "142") (name "unconnected-(J1-Pad12)") (class "Default")
      (node (ref "J1") (pin "12") (pinfunction "12_12") (pintype "passive"))
    )
    (net (code "143") (name "unconnected-(J1-Pad13)") (class "Default")
      (node (ref "J1") (pin "13") (pinfunction "13_13") (pintype "passive"))
    )
    (net (code "144") (name "unconnected-(J1-Pad14)") (class "Default")
      (node (ref "J1") (pin "14") (pinfunction "14_14") (pintype "passive"))
    )
    (net (code "145") (name "unconnected-(J1-Pad15)") (class "Default")
      (node (ref "J1") (pin "15") (pinfunction "15_15") (pintype "passive"))
    )
    (net (code "146") (name "unconnected-(J1-Pad16)") (class "Default")
      (node (ref "J1") (pin "16") (pinfunction "16_16") (pintype "passive"))
    )
    (net (code "147") (name "unconnected-(J1-Pad17)") (class "Default")
      (node (ref "J1") (pin "17") (pinfunction "17_17") (pintype "passive"))
    )
    (net (code "148") (name "unconnected-(J1-Pad18)") (class "Default")
      (node (ref "J1") (pin "18") (pinfunction "18_18") (pintype "passive"))
    )
    (net (code "149") (name "unconnected-(J1-Pad19)") (class "Default")
      (node (ref "J1") (pin "19") (pinfunction "19_19") (pintype "passive"))
    )
    (net (code "150") (name "unconnected-(J1-Pad20)") (class "Default")
      (node (ref "J1") (pin "20") (pinfunction "20_20") (pintype "passive"))
    )
    (net (code "151") (name "unconnected-(U1A-PA8-Pad100)") (class "Default")
      (node (ref "U1") (pin "100") (pinfunction "PA8_100") (pintype "bidirectional"))
    )
    (net (code "152") (name "unconnected-(U1A-PB4(NJTRST)-Pad134)") (class "Default")
      (node (ref "U1") (pin "134") (pinfunction "PB4(NJTRST)_134") (pintype "bidirectional"))
    )
    (net (code "153") (name "unconnected-(U1A-PB5-Pad135)") (class "Default")
      (node (ref "U1") (pin "135") (pinfunction "PB5_135") (pintype "bidirectional"))
    )
    (net (code "154") (name "unconnected-(U1A-PB6-Pad136)") (class "Default")
      (node (ref "U1") (pin "136") (pinfunction "PB6_136") (pintype "bidirectional"))
    )
    (net (code "155") (name "unconnected-(U1A-PB7-Pad137)") (class "Default")
      (node (ref "U1") (pin "137") (pinfunction "PB7_137") (pintype "bidirectional"))
    )
    (net (code "156") (name "unconnected-(U1A-PB8-Pad139)") (class "Default")
      (node (ref "U1") (pin "139") (pinfunction "PB8_139") (pintype "bidirectional"))
    )
    (net (code "157") (name "unconnected-(U1A-PB9-Pad140)") (class "Default")
      (node (ref "U1") (pin "140") (pinfunction "PB9_140") (pintype "bidirectional"))
    )
    (net (code "158") (name "unconnected-(U1A-PB14-Pad75)") (class "Default")
      (node (ref "U1") (pin "75") (pinfunction "PB14_75") (pintype "bidirectional"))
    )
    (net (code "159") (name "unconnected-(U1A-PB15-Pad76)") (class "Default")
      (node (ref "U1") (pin "76") (pinfunction "PB15_76") (pintype "bidirectional"))
    )
    (net (code "160") (name "unconnected-(U1A-PC13-Pad7)") (class "Default")
      (node (ref "U1") (pin "7") (pinfunction "PC13_7") (pintype "bidirectional"))
    )
    (net (code "161") (name "unconnected-(U1A-PD0-Pad114)") (class "Default")
      (node (ref "U1") (pin "114") (pinfunction "PD0_114") (pintype "bidirectional"))
    )
    (net (code "162") (name "unconnected-(U1A-PD1-Pad115)") (class "Default")
      (node (ref "U1") (pin "115") (pinfunction "PD1_115") (pintype "bidirectional"))
    )
    (net (code "163") (name "unconnected-(U1A-PD3-Pad117)") (class "Default")
      (node (ref "U1") (pin "117") (pinfunction "PD3_117") (pintype "bidirectional"))
    )
    (net (code "164") (name "unconnected-(U1A-PD4-Pad118)") (class "Default")
      (node (ref "U1") (pin "118") (pinfunction "PD4_118") (pintype "bidirectional"))
    )
    (net (code "165") (name "unconnected-(U1A-PD7-Pad123)") (class "Default")
      (node (ref "U1") (pin "123") (pinfunction "PD7_123") (pintype "bidirectional"))
    )
    (net (code "166") (name "unconnected-(U1A-PD11-Pad80)") (class "Default")
      (node (ref "U1") (pin "80") (pinfunction "PD11_80") (pintype "bidirectional"))
    )
    (net (code "167") (name "unconnected-(U1B-PE0-Pad141)") (class "Default")
      (node (ref "U1") (pin "141") (pinfunction "PE0_141") (pintype "bidirectional"))
    )
    (net (code "168") (name "unconnected-(U1B-PE1-Pad142)") (class "Default")
      (node (ref "U1") (pin "142") (pinfunction "PE1_142") (pintype "bidirectional"))
    )
    (net (code "169") (name "unconnected-(U1B-PE2-Pad1)") (class "Default")
      (node (ref "U1") (pin "1") (pinfunction "PE2_1") (pintype "bidirectional"))
    )
    (net (code "170") (name "unconnected-(U1B-PE3-Pad2)") (class "Default")
      (node (ref "U1") (pin "2") (pinfunction "PE3_2") (pintype "bidirectional"))
    )
    (net (code "171") (name "unconnected-(U1B-PE4-Pad3)") (class "Default")
      (node (ref "U1") (pin "3") (pinfunction "PE4_3") (pintype "bidirectional"))
    )
    (net (code "172") (name "unconnected-(U1B-PE5-Pad4)") (class "Default")
      (node (ref "U1") (pin "4") (pinfunction "PE5_4") (pintype "bidirectional"))
    )
    (net (code "173") (name "unconnected-(U1B-PE6-Pad5)") (class "Default")
      (node (ref "U1") (pin "5") (pinfunction "PE6_5") (pintype "bidirectional"))
    )
    (net (code "174") (name "unconnected-(U1B-PE10-Pad63)") (class "Default")
      (node (ref "U1") (pin "63") (pinfunction "PE10_63") (pintype "bidirectional"))
    )
    (net (code "175") (name "unconnected-(U1B-PE12-Pad65)") (class "Default")
      (node (ref "U1") (pin "65") (pinfunction "PE12_65") (pintype "bidirectional"))
    )
    (net (code "176") (name "unconnected-(U1B-PE15-Pad68)") (class "Default")
      (node (ref "U1") (pin "68") (pinfunction "PE15_68") (pintype "bidirectional"))
    )
    (net (code "177") (name "unconnected-(U1B-PF0-Pad10)") (class "Default")
      (node (ref "U1") (pin "10") (pinfunction "PF0_10") (pintype "bidirectional"))
    )
    (net (code "178") (name "unconnected-(U1B-PF1-Pad11)") (class "Default")
      (node (ref "U1") (pin "11") (pinfunction "PF1_11") (pintype "bidirectional"))
    )
    (net (code "179") (name "unconnected-(U1B-PF2-Pad12)") (class "Default")
      (node (ref "U1") (pin "12") (pinfunction "PF2_12") (pintype "bidirectional"))
    )
    (net (code "180") (name "unconnected-(U1B-PF11-Pad49)") (class "Default")
      (node (ref "U1") (pin "49") (pinfunction "PF11_49") (pintype "bidirectional"))
    )
    (net (code "181") (name "unconnected-(U1B-PF12-Pad50)") (class "Default")
      (node (ref "U1") (pin "50") (pinfunction "PF12_50") (pintype "bidirectional"))
    )
    (net (code "182") (name "unconnected-(U1B-PF13-Pad53)") (class "Default")
      (node (ref "U1") (pin "53") (pinfunction "PF13_53") (pintype "bidirectional"))
    )
    (net (code "183") (name "unconnected-(U1B-PF14-Pad54)") (class "Default")
      (node (ref "U1") (pin "54") (pinfunction "PF14_54") (pintype "bidirectional"))
    )
    (net (code "184") (name "unconnected-(U1B-PF15-Pad55)") (class "Default")
      (node (ref "U1") (pin "55") (pinfunction "PF15_55") (pintype "bidirectional"))
    )
    (net (code "185") (name "unconnected-(U1B-PG0-Pad56)") (class "Default")
      (node (ref "U1") (pin "56") (pinfunction "PG0_56") (pintype "bidirectional"))
    )
    (net (code "186") (name "unconnected-(U1B-PG1-Pad57)") (class "Default")
      (node (ref "U1") (pin "57") (pinfunction "PG1_57") (pintype "bidirectional"))
    )
    (net (code "187") (name "unconnected-(U1B-PG2-Pad87)") (class "Default")
      (node (ref "U1") (pin "87") (pinfunction "PG2_87") (pintype "bidirectional"))
    )
    (net (code "188") (name "unconnected-(U1B-PG3-Pad88)") (class "Default")
      (node (ref "U1") (pin "88") (pinfunction "PG3_88") (pintype "bidirectional"))
    )
    (net (code "189") (name "unconnected-(U1B-PG4-Pad89)") (class "Default")
      (node (ref "U1") (pin "89") (pinfunction "PG4_89") (pintype "bidirectional"))
    )
    (net (code "190") (name "unconnected-(U1B-PG5-Pad90)") (class "Default")
      (node (ref "U1") (pin "90") (pinfunction "PG5_90") (pintype "bidirectional"))
    )
    (net (code "191") (name "unconnected-(U1B-PG6-Pad91)") (class "Default")
      (node (ref "U1") (pin "91") (pinfunction "PG6_91") (pintype "bidirectional"))
    )
    (net (code "192") (name "unconnected-(U1B-PG7-Pad92)") (class "Default")
      (node (ref "U1") (pin "92") (pinfunction "PG7_92") (pintype "bidirectional"))
    )
    (net (code "193") (name "unconnected-(U1B-PG8-Pad93)") (class "Default")
      (node (ref "U1") (pin "93") (pinfunction "PG8_93") (pintype "bidirectional"))
    )
    (net (code "194") (name "unconnected-(U1B-PG9-Pad124)") (class "Default")
      (node (ref "U1") (pin "124") (pinfunction "PG9_124") (pintype "bidirectional"))
    )
    (net (code "195") (name "unconnected-(U1B-PG10-Pad125)") (class "Default")
      (node (ref "U1") (pin "125") (pinfunction "PG10_125") (pintype "bidirectional"))
    )
    (net (code "196") (name "unconnected-(U1B-PG11-Pad126)") (class "Default")
      (node (ref "U1") (pin "126") (pinfunction "PG11_126") (pintype "bidirectional"))
    )
    (net (code "197") (name "unconnected-(U1B-PG12-Pad127)") (class "Default")
      (node (ref "U1") (pin "127") (pinfunction "PG12_127") (pintype "bidirectional"))
    )
    (net (code "198") (name "unconnected-(U1B-PG13-Pad128)") (class "Default")
      (node (ref "U1") (pin "128") (pinfunction "PG13_128") (pintype "bidirectional"))
    )
    (net (code "199") (name "unconnected-(U1B-PG14-Pad129)") (class "Default")
      (node (ref "U1") (pin "129") (pinfunction "PG14_129") (pintype "bidirectional"))
    )
    (net (code "200") (name "unconnected-(U1B-PG15-Pad132)") (class "Default")
      (node (ref "U1") (pin "132") (pinfunction "PG15_132") (pintype "bidirectional"))
    )
  )
)
